# daughterboard.net
KiCad netlist of a schematic drawn in EAGLE
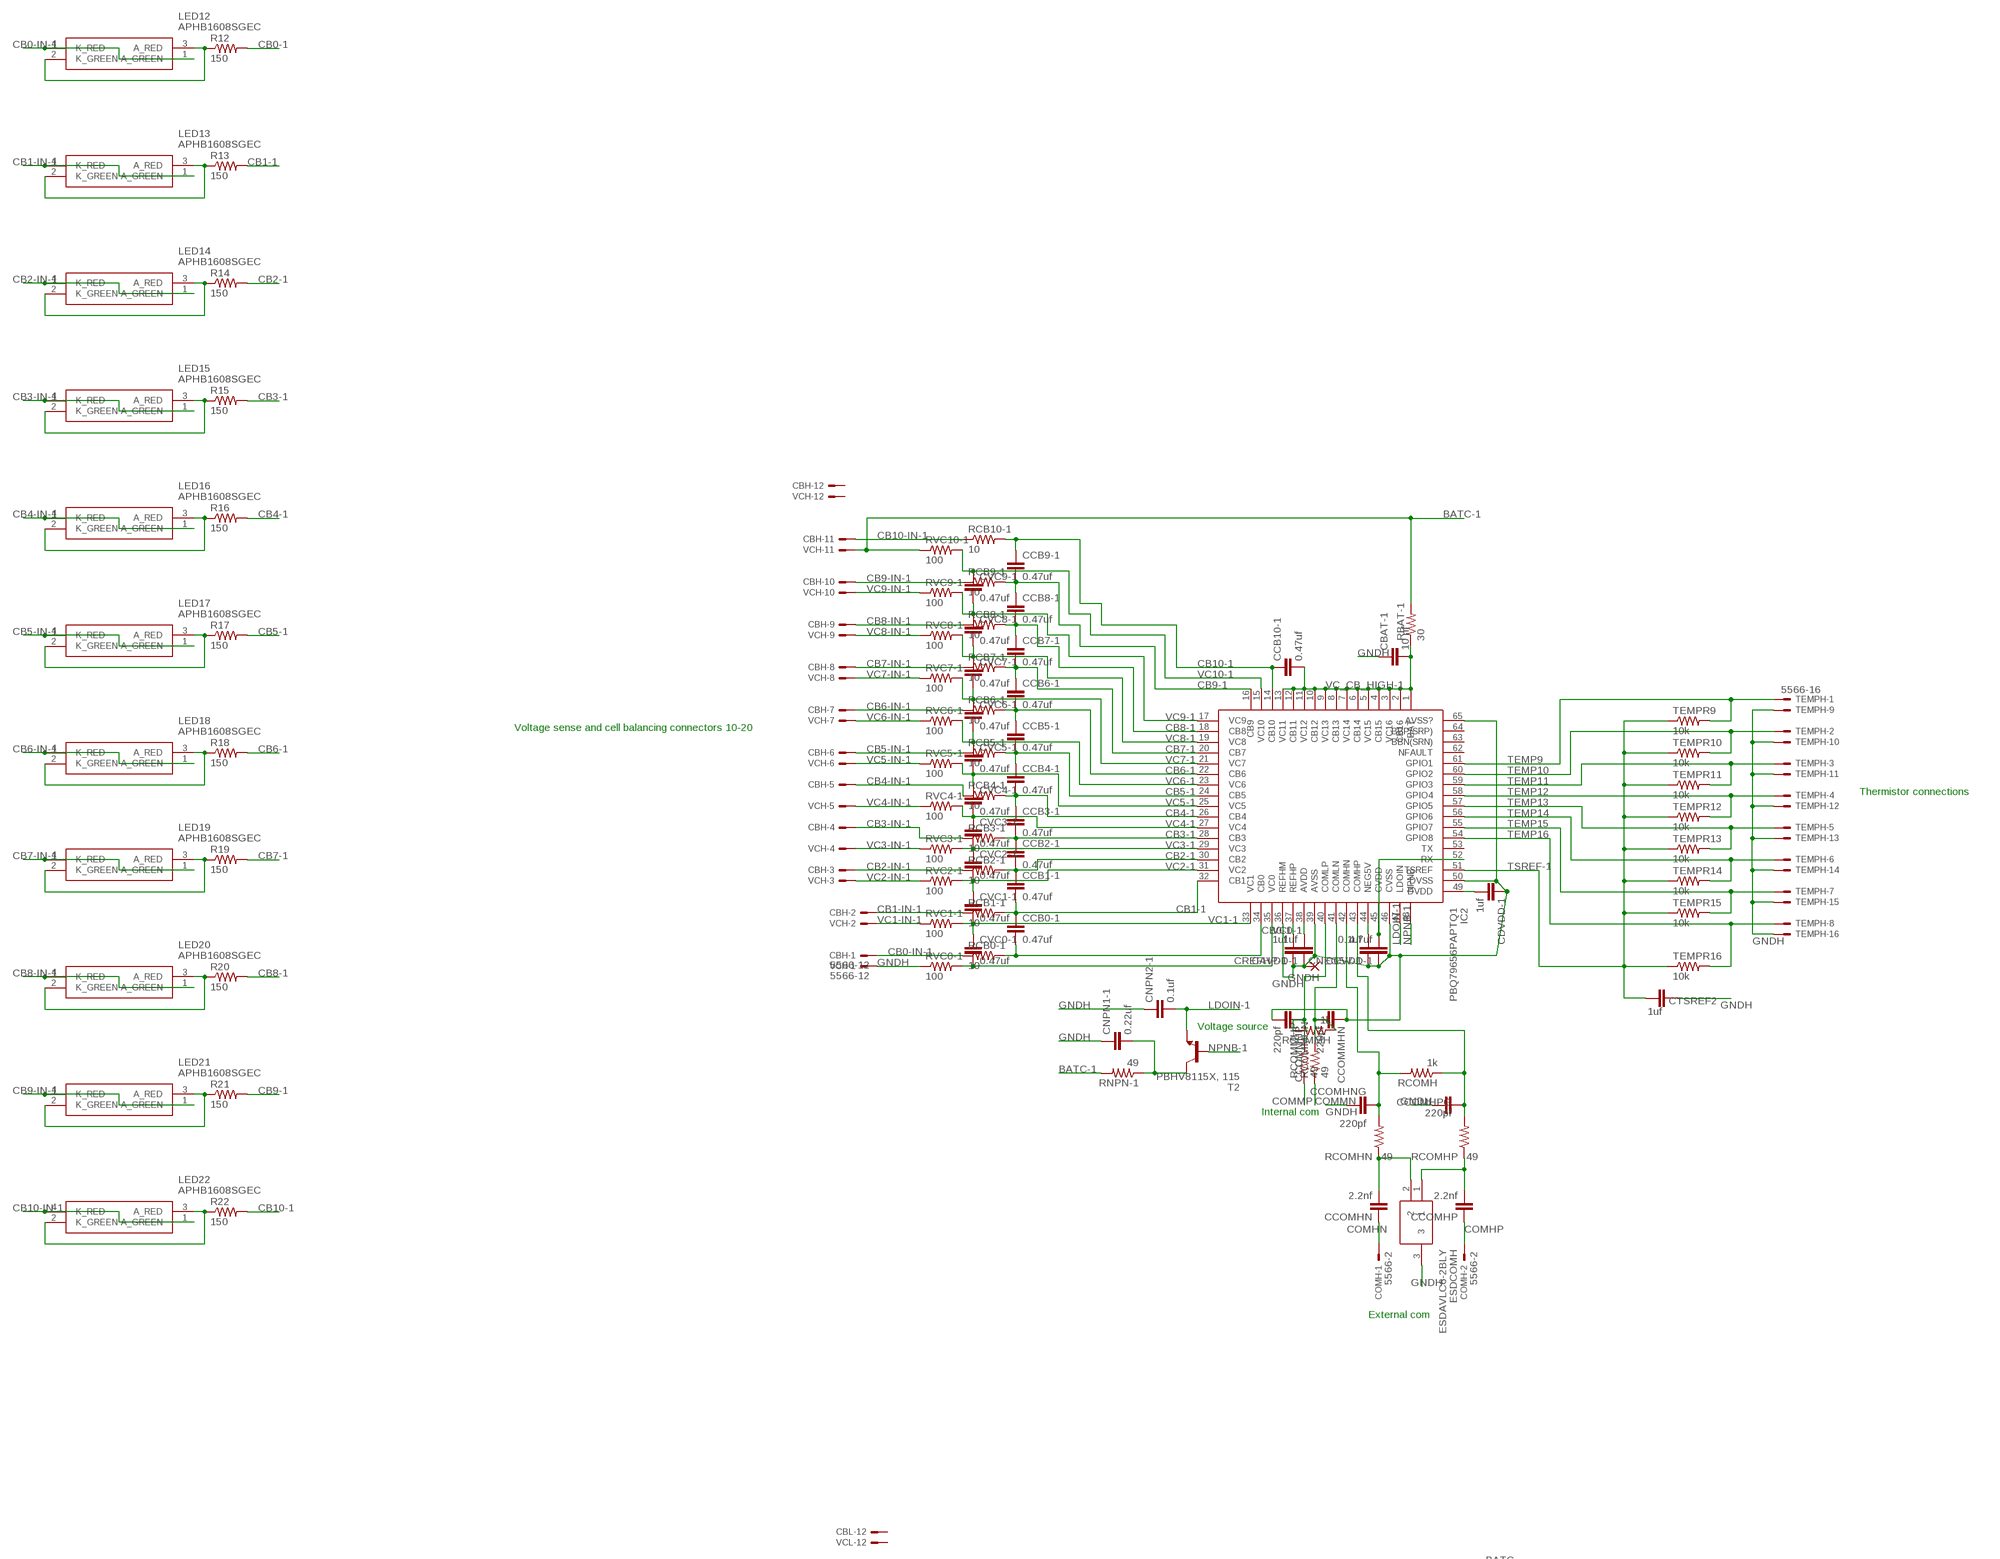
[diagram p0: schematic, sheet 1, part 1 of 2]
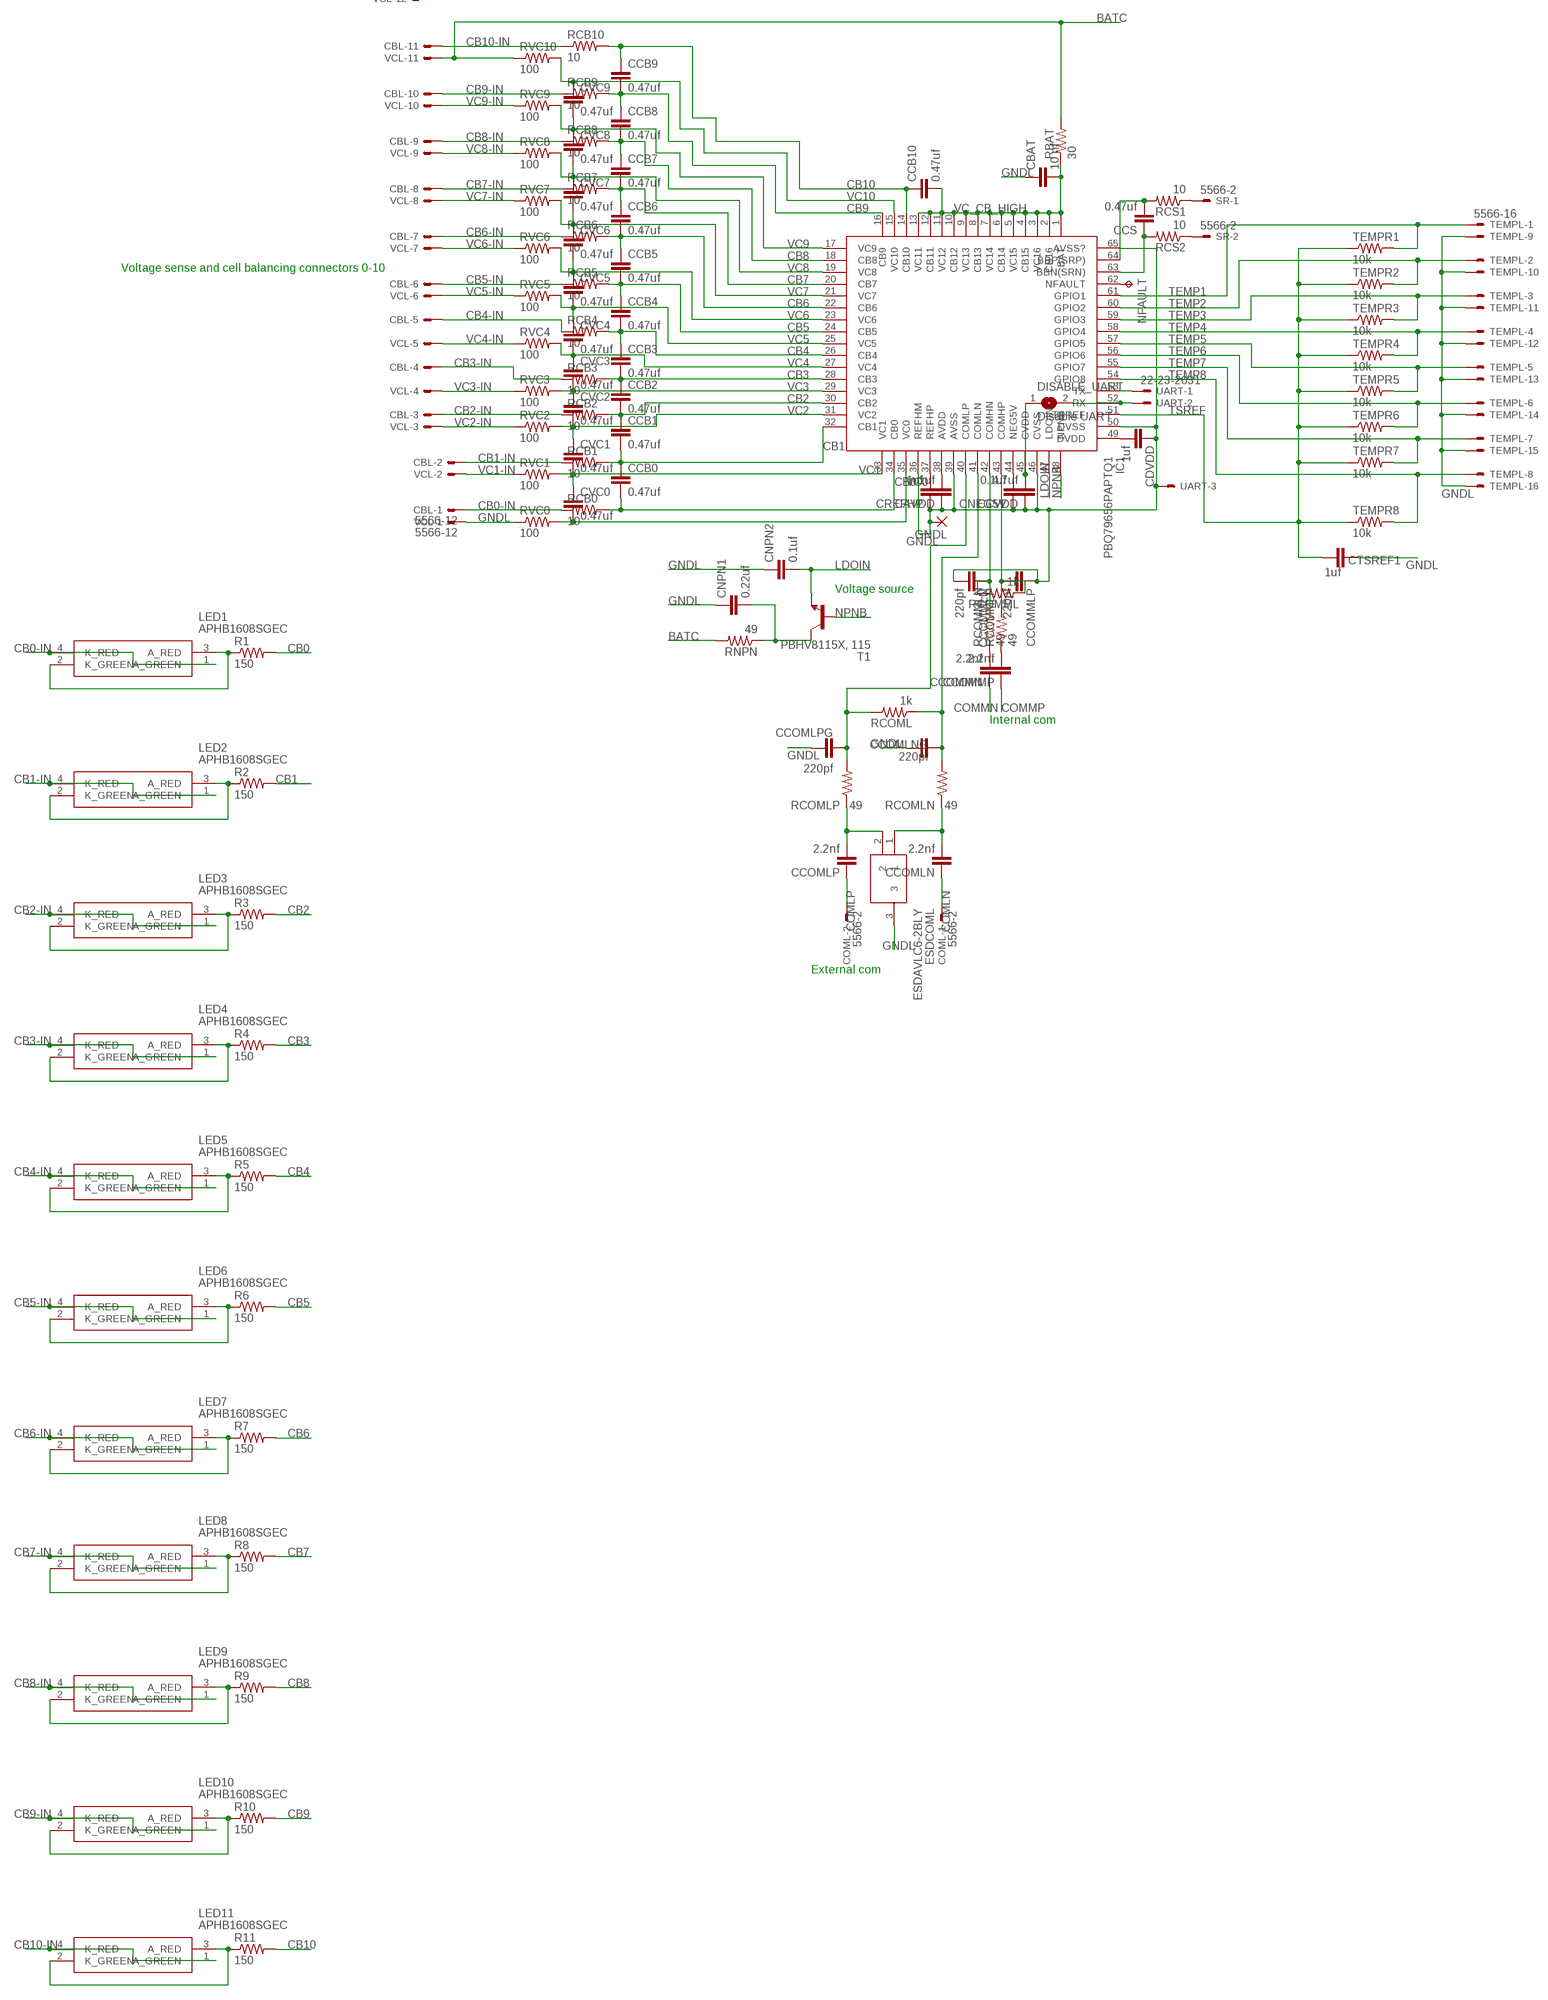
[diagram p1: schematic, sheet 1, part 2 of 2]

(export (version "E")
  (design (tool "Eeschema 10.0.6"))
  (components
    (comp (ref "CAVDD")
      (value "1uf")
      (footprint "eagle-import:C0603")
      (libsource (lib "eagle-import") (part "C-EUC0603"))
    )
    (comp (ref "CAVDD-1")
      (value "1uf")
      (footprint "eagle-import:C0603")
      (libsource (lib "eagle-import") (part "C-EUC0603"))
    )
    (comp (ref "CBAT")
      (value "10 nf")
      (footprint "eagle-import:C0603")
      (libsource (lib "eagle-import") (part "C-EUC0603"))
    )
    (comp (ref "CBAT-1")
      (value "10 nf")
      (footprint "eagle-import:C0603")
      (libsource (lib "eagle-import") (part "C-EUC0603"))
    )
    (comp (ref "CBH")
      (value "5566-12")
      (footprint "eagle-import:5566-12")
      (fields (field (name "MF") "MOLEX"))
      (libsource (lib "eagle-import") (part "5566-12"))
    )
    (comp (ref "CBL")
      (value "5566-12")
      (footprint "eagle-import:5566-12")
      (fields (field (name "MF") "MOLEX"))
      (libsource (lib "eagle-import") (part "5566-12"))
    )
    (comp (ref "CCB0")
      (value "0.47uf")
      (footprint "eagle-import:C0603")
      (libsource (lib "eagle-import") (part "C-EUC0603"))
    )
    (comp (ref "CCB0-1")
      (value "0.47uf")
      (footprint "eagle-import:C0603")
      (libsource (lib "eagle-import") (part "C-EUC0603"))
    )
    (comp (ref "CCB1")
      (value "0.47uf")
      (footprint "eagle-import:C0603")
      (libsource (lib "eagle-import") (part "C-EUC0603"))
    )
    (comp (ref "CCB1-1")
      (value "0.47uf")
      (footprint "eagle-import:C0603")
      (libsource (lib "eagle-import") (part "C-EUC0603"))
    )
    (comp (ref "CCB2")
      (value "0.47uf")
      (footprint "eagle-import:C0603")
      (libsource (lib "eagle-import") (part "C-EUC0603"))
    )
    (comp (ref "CCB2-1")
      (value "0.47uf")
      (footprint "eagle-import:C0603")
      (libsource (lib "eagle-import") (part "C-EUC0603"))
    )
    (comp (ref "CCB3")
      (value "0.47uf")
      (footprint "eagle-import:C0603")
      (libsource (lib "eagle-import") (part "C-EUC0603"))
    )
    (comp (ref "CCB3-1")
      (value "0.47uf")
      (footprint "eagle-import:C0603")
      (libsource (lib "eagle-import") (part "C-EUC0603"))
    )
    (comp (ref "CCB4")
      (value "0.47uf")
      (footprint "eagle-import:C0603")
      (libsource (lib "eagle-import") (part "C-EUC0603"))
    )
    (comp (ref "CCB4-1")
      (value "0.47uf")
      (footprint "eagle-import:C0603")
      (libsource (lib "eagle-import") (part "C-EUC0603"))
    )
    (comp (ref "CCB5")
      (value "0.47uf")
      (footprint "eagle-import:C0603")
      (libsource (lib "eagle-import") (part "C-EUC0603"))
    )
    (comp (ref "CCB5-1")
      (value "0.47uf")
      (footprint "eagle-import:C0603")
      (libsource (lib "eagle-import") (part "C-EUC0603"))
    )
    (comp (ref "CCB6")
      (value "0.47uf")
      (footprint "eagle-import:C0603")
      (libsource (lib "eagle-import") (part "C-EUC0603"))
    )
    (comp (ref "CCB6-1")
      (value "0.47uf")
      (footprint "eagle-import:C0603")
      (libsource (lib "eagle-import") (part "C-EUC0603"))
    )
    (comp (ref "CCB7")
      (value "0.47uf")
      (footprint "eagle-import:C0603")
      (libsource (lib "eagle-import") (part "C-EUC0603"))
    )
    (comp (ref "CCB7-1")
      (value "0.47uf")
      (footprint "eagle-import:C0603")
      (libsource (lib "eagle-import") (part "C-EUC0603"))
    )
    (comp (ref "CCB8")
      (value "0.47uf")
      (footprint "eagle-import:C0603")
      (libsource (lib "eagle-import") (part "C-EUC0603"))
    )
    (comp (ref "CCB8-1")
      (value "0.47uf")
      (footprint "eagle-import:C0603")
      (libsource (lib "eagle-import") (part "C-EUC0603"))
    )
    (comp (ref "CCB9")
      (value "0.47uf")
      (footprint "eagle-import:C0603")
      (libsource (lib "eagle-import") (part "C-EUC0603"))
    )
    (comp (ref "CCB9-1")
      (value "0.47uf")
      (footprint "eagle-import:C0603")
      (libsource (lib "eagle-import") (part "C-EUC0603"))
    )
    (comp (ref "CCB10")
      (value "0.47uf")
      (footprint "eagle-import:C0603")
      (libsource (lib "eagle-import") (part "C-EUC0603"))
    )
    (comp (ref "CCB10-1")
      (value "0.47uf")
      (footprint "eagle-import:C0603")
      (libsource (lib "eagle-import") (part "C-EUC0603"))
    )
    (comp (ref "CCOMHN")
      (value "2.2nf")
      (footprint "eagle-import:C0603")
      (libsource (lib "eagle-import") (part "C-EUC0603"))
    )
    (comp (ref "CCOMHNG")
      (value "220pf")
      (footprint "eagle-import:C0603")
      (libsource (lib "eagle-import") (part "C-EUC0603"))
    )
    (comp (ref "CCOMHP")
      (value "2.2nf")
      (footprint "eagle-import:C0603")
      (libsource (lib "eagle-import") (part "C-EUC0603"))
    )
    (comp (ref "CCOMHPG")
      (value "220pf")
      (footprint "eagle-import:C0603")
      (libsource (lib "eagle-import") (part "C-EUC0603"))
    )
    (comp (ref "CCOMLN")
      (value "2.2nf")
      (footprint "eagle-import:C0603")
      (libsource (lib "eagle-import") (part "C-EUC0603"))
    )
    (comp (ref "CCOMLNG")
      (value "220pf")
      (footprint "eagle-import:C0603")
      (libsource (lib "eagle-import") (part "C-EUC0603"))
    )
    (comp (ref "CCOMLP")
      (value "2.2nf")
      (footprint "eagle-import:C0603")
      (libsource (lib "eagle-import") (part "C-EUC0603"))
    )
    (comp (ref "CCOMLPG")
      (value "220pf")
      (footprint "eagle-import:C0603")
      (libsource (lib "eagle-import") (part "C-EUC0603"))
    )
    (comp (ref "CCOMMHN")
      (value "220pf")
      (footprint "eagle-import:C0603")
      (libsource (lib "eagle-import") (part "C-EUC0603"))
    )
    (comp (ref "CCOMMHP")
      (value "220pf")
      (footprint "eagle-import:C0603")
      (libsource (lib "eagle-import") (part "C-EUC0603"))
    )
    (comp (ref "CCOMMLN")
      (value "220pf")
      (footprint "eagle-import:C0603")
      (libsource (lib "eagle-import") (part "C-EUC0603"))
    )
    (comp (ref "CCOMMLP")
      (value "220pf")
      (footprint "eagle-import:C0603")
      (libsource (lib "eagle-import") (part "C-EUC0603"))
    )
    (comp (ref "CCOMMN")
      (value "2.2nf")
      (footprint "eagle-import:C0603")
      (libsource (lib "eagle-import") (part "C-EUC0603"))
    )
    (comp (ref "CCOMMP")
      (value "2.2nf")
      (footprint "eagle-import:C0603")
      (libsource (lib "eagle-import") (part "C-EUC0603"))
    )
    (comp (ref "CCS")
      (value "0.47uf")
      (footprint "eagle-import:C0603")
      (libsource (lib "eagle-import") (part "C-EUC0603"))
    )
    (comp (ref "CCVDD")
      (value "4.7uf")
      (footprint "eagle-import:C0603")
      (libsource (lib "eagle-import") (part "C-EUC0603"))
    )
    (comp (ref "CCVDD-1")
      (value "4.7uf")
      (footprint "eagle-import:C0603")
      (libsource (lib "eagle-import") (part "C-EUC0603"))
    )
    (comp (ref "CDVDD")
      (value "1uf")
      (footprint "eagle-import:C0603")
      (libsource (lib "eagle-import") (part "C-EUC0603"))
    )
    (comp (ref "CDVDD-1")
      (value "1uf")
      (footprint "eagle-import:C0603")
      (libsource (lib "eagle-import") (part "C-EUC0603"))
    )
    (comp (ref "CNEG5V")
      (value "0.1uf")
      (footprint "eagle-import:C0603")
      (libsource (lib "eagle-import") (part "C-EUC0603"))
    )
    (comp (ref "CNEG5V-1")
      (value "0.1uf")
      (footprint "eagle-import:C0603")
      (libsource (lib "eagle-import") (part "C-EUC0603"))
    )
    (comp (ref "CNPN1")
      (value "0.22uf")
      (footprint "eagle-import:C0603")
      (libsource (lib "eagle-import") (part "C-EUC0603"))
    )
    (comp (ref "CNPN1-1")
      (value "0.22uf")
      (footprint "eagle-import:C0603")
      (libsource (lib "eagle-import") (part "C-EUC0603"))
    )
    (comp (ref "CNPN2")
      (value "0.1uf")
      (footprint "eagle-import:C0603")
      (libsource (lib "eagle-import") (part "C-EUC0603"))
    )
    (comp (ref "CNPN2-1")
      (value "0.1uf")
      (footprint "eagle-import:C0603")
      (libsource (lib "eagle-import") (part "C-EUC0603"))
    )
    (comp (ref "COMH")
      (value "5566-2")
      (footprint "eagle-import:5566-2")
      (fields (field (name "MF") "MOLEX"))
      (libsource (lib "eagle-import") (part "5566-2"))
    )
    (comp (ref "COML")
      (value "5566-2")
      (footprint "eagle-import:5566-2")
      (fields (field (name "MF") "MOLEX"))
      (libsource (lib "eagle-import") (part "5566-2"))
    )
    (comp (ref "CREFHP")
      (value "1uf")
      (footprint "eagle-import:C0603")
      (libsource (lib "eagle-import") (part "C-EUC0603"))
    )
    (comp (ref "CREFHP-1")
      (value "1uf")
      (footprint "eagle-import:C0603")
      (libsource (lib "eagle-import") (part "C-EUC0603"))
    )
    (comp (ref "CTSREF1")
      (value "1uf")
      (footprint "eagle-import:C0603")
      (libsource (lib "eagle-import") (part "C-EUC0603"))
    )
    (comp (ref "CTSREF2")
      (value "1uf")
      (footprint "eagle-import:C0603")
      (libsource (lib "eagle-import") (part "C-EUC0603"))
    )
    (comp (ref "CVC0")
      (value "0.47uf")
      (footprint "eagle-import:C0603")
      (libsource (lib "eagle-import") (part "C-EUC0603"))
    )
    (comp (ref "CVC0-1")
      (value "0.47uf")
      (footprint "eagle-import:C0603")
      (libsource (lib "eagle-import") (part "C-EUC0603"))
    )
    (comp (ref "CVC1")
      (value "0.47uf")
      (footprint "eagle-import:C0603")
      (libsource (lib "eagle-import") (part "C-EUC0603"))
    )
    (comp (ref "CVC1-1")
      (value "0.47uf")
      (footprint "eagle-import:C0603")
      (libsource (lib "eagle-import") (part "C-EUC0603"))
    )
    (comp (ref "CVC2")
      (value "0.47uf")
      (footprint "eagle-import:C0603")
      (libsource (lib "eagle-import") (part "C-EUC0603"))
    )
    (comp (ref "CVC2-1")
      (value "0.47uf")
      (footprint "eagle-import:C0603")
      (libsource (lib "eagle-import") (part "C-EUC0603"))
    )
    (comp (ref "CVC3")
      (value "0.47uf")
      (footprint "eagle-import:C0603")
      (libsource (lib "eagle-import") (part "C-EUC0603"))
    )
    (comp (ref "CVC3-1")
      (value "0.47uf")
      (footprint "eagle-import:C0603")
      (libsource (lib "eagle-import") (part "C-EUC0603"))
    )
    (comp (ref "CVC4")
      (value "0.47uf")
      (footprint "eagle-import:C0603")
      (libsource (lib "eagle-import") (part "C-EUC0603"))
    )
    (comp (ref "CVC4-1")
      (value "0.47uf")
      (footprint "eagle-import:C0603")
      (libsource (lib "eagle-import") (part "C-EUC0603"))
    )
    (comp (ref "CVC5")
      (value "0.47uf")
      (footprint "eagle-import:C0603")
      (libsource (lib "eagle-import") (part "C-EUC0603"))
    )
    (comp (ref "CVC5-1")
      (value "0.47uf")
      (footprint "eagle-import:C0603")
      (libsource (lib "eagle-import") (part "C-EUC0603"))
    )
    (comp (ref "CVC6")
      (value "0.47uf")
      (footprint "eagle-import:C0603")
      (libsource (lib "eagle-import") (part "C-EUC0603"))
    )
    (comp (ref "CVC6-1")
      (value "0.47uf")
      (footprint "eagle-import:C0603")
      (libsource (lib "eagle-import") (part "C-EUC0603"))
    )
    (comp (ref "CVC7")
      (value "0.47uf")
      (footprint "eagle-import:C0603")
      (libsource (lib "eagle-import") (part "C-EUC0603"))
    )
    (comp (ref "CVC7-1")
      (value "0.47uf")
      (footprint "eagle-import:C0603")
      (libsource (lib "eagle-import") (part "C-EUC0603"))
    )
    (comp (ref "CVC8")
      (value "0.47uf")
      (footprint "eagle-import:C0603")
      (libsource (lib "eagle-import") (part "C-EUC0603"))
    )
    (comp (ref "CVC8-1")
      (value "0.47uf")
      (footprint "eagle-import:C0603")
      (libsource (lib "eagle-import") (part "C-EUC0603"))
    )
    (comp (ref "CVC9")
      (value "0.47uf")
      (footprint "eagle-import:C0603")
      (libsource (lib "eagle-import") (part "C-EUC0603"))
    )
    (comp (ref "CVC9-1")
      (value "0.47uf")
      (footprint "eagle-import:C0603")
      (libsource (lib "eagle-import") (part "C-EUC0603"))
    )
    (comp (ref "DISABLE_UART")
      (value "Disable UART")
      (footprint "eagle-import:SJ")
      (libsource (lib "eagle-import") (part "SJ"))
    )
    (comp (ref "ESDCOMH")
      (value "ESDAVLC6-2BLY")
      (footprint "eagle-import:SOT95P255X150-3N")
      (fields (field (name "MOUSER_PART_NUMBER") "511-ESDAVLC6-2BLY"))
      (libsource (lib "eagle-import") (part "ESDAVLC6-2BLY"))
    )
    (comp (ref "ESDCOML")
      (value "ESDAVLC6-2BLY")
      (footprint "eagle-import:SOT95P255X150-3N")
      (fields (field (name "MOUSER_PART_NUMBER") "511-ESDAVLC6-2BLY"))
      (libsource (lib "eagle-import") (part "ESDAVLC6-2BLY"))
    )
    (comp (ref "GNDH")
      (value "SMD5")
      (footprint "eagle-import:SMD2,54-5,08")
      (libsource (lib "eagle-import") (part "SMD5"))
    )
    (comp (ref "GNDL")
      (value "SMD5")
      (footprint "eagle-import:SMD2,54-5,08")
      (libsource (lib "eagle-import") (part "SMD5"))
    )
    (comp (ref "IC1")
      (value "PBQ79656PAPTQ1")
      (footprint "eagle-import:QFP50P1200X1200X120-65N")
      (libsource (lib "eagle-import") (part "PBQ79656PAPTQ1"))
    )
    (comp (ref "IC2")
      (value "PBQ79656PAPTQ1")
      (footprint "eagle-import:QFP50P1200X1200X120-65N")
      (libsource (lib "eagle-import") (part "PBQ79656PAPTQ1"))
    )
    (comp (ref "LED1")
      (value "APHB1608SGEC")
      (footprint "eagle-import:APHB1608SGEC")
      (fields (field (name "MOUSER_PART_NUMBER") "604-APHB1608SGEC"))
      (libsource (lib "eagle-import") (part "APHB1608SGEC"))
    )
    (comp (ref "LED2")
      (value "APHB1608SGEC")
      (footprint "eagle-import:APHB1608SGEC")
      (fields (field (name "MOUSER_PART_NUMBER") "604-APHB1608SGEC"))
      (libsource (lib "eagle-import") (part "APHB1608SGEC"))
    )
    (comp (ref "LED3")
      (value "APHB1608SGEC")
      (footprint "eagle-import:APHB1608SGEC")
      (fields (field (name "MOUSER_PART_NUMBER") "604-APHB1608SGEC"))
      (libsource (lib "eagle-import") (part "APHB1608SGEC"))
    )
    (comp (ref "LED4")
      (value "APHB1608SGEC")
      (footprint "eagle-import:APHB1608SGEC")
      (fields (field (name "MOUSER_PART_NUMBER") "604-APHB1608SGEC"))
      (libsource (lib "eagle-import") (part "APHB1608SGEC"))
    )
    (comp (ref "LED5")
      (value "APHB1608SGEC")
      (footprint "eagle-import:APHB1608SGEC")
      (fields (field (name "MOUSER_PART_NUMBER") "604-APHB1608SGEC"))
      (libsource (lib "eagle-import") (part "APHB1608SGEC"))
    )
    (comp (ref "LED6")
      (value "APHB1608SGEC")
      (footprint "eagle-import:APHB1608SGEC")
      (fields (field (name "MOUSER_PART_NUMBER") "604-APHB1608SGEC"))
      (libsource (lib "eagle-import") (part "APHB1608SGEC"))
    )
    (comp (ref "LED7")
      (value "APHB1608SGEC")
      (footprint "eagle-import:APHB1608SGEC")
      (fields (field (name "MOUSER_PART_NUMBER") "604-APHB1608SGEC"))
      (libsource (lib "eagle-import") (part "APHB1608SGEC"))
    )
    (comp (ref "LED8")
      (value "APHB1608SGEC")
      (footprint "eagle-import:APHB1608SGEC")
      (fields (field (name "MOUSER_PART_NUMBER") "604-APHB1608SGEC"))
      (libsource (lib "eagle-import") (part "APHB1608SGEC"))
    )
    (comp (ref "LED9")
      (value "APHB1608SGEC")
      (footprint "eagle-import:APHB1608SGEC")
      (fields (field (name "MOUSER_PART_NUMBER") "604-APHB1608SGEC"))
      (libsource (lib "eagle-import") (part "APHB1608SGEC"))
    )
    (comp (ref "LED10")
      (value "APHB1608SGEC")
      (footprint "eagle-import:APHB1608SGEC")
      (fields (field (name "MOUSER_PART_NUMBER") "604-APHB1608SGEC"))
      (libsource (lib "eagle-import") (part "APHB1608SGEC"))
    )
    (comp (ref "LED11")
      (value "APHB1608SGEC")
      (footprint "eagle-import:APHB1608SGEC")
      (fields (field (name "MOUSER_PART_NUMBER") "604-APHB1608SGEC"))
      (libsource (lib "eagle-import") (part "APHB1608SGEC"))
    )
    (comp (ref "LED12")
      (value "APHB1608SGEC")
      (footprint "eagle-import:APHB1608SGEC")
      (fields (field (name "MOUSER_PART_NUMBER") "604-APHB1608SGEC"))
      (libsource (lib "eagle-import") (part "APHB1608SGEC"))
    )
    (comp (ref "LED13")
      (value "APHB1608SGEC")
      (footprint "eagle-import:APHB1608SGEC")
      (fields (field (name "MOUSER_PART_NUMBER") "604-APHB1608SGEC"))
      (libsource (lib "eagle-import") (part "APHB1608SGEC"))
    )
    (comp (ref "LED14")
      (value "APHB1608SGEC")
      (footprint "eagle-import:APHB1608SGEC")
      (fields (field (name "MOUSER_PART_NUMBER") "604-APHB1608SGEC"))
      (libsource (lib "eagle-import") (part "APHB1608SGEC"))
    )
    (comp (ref "LED15")
      (value "APHB1608SGEC")
      (footprint "eagle-import:APHB1608SGEC")
      (fields (field (name "MOUSER_PART_NUMBER") "604-APHB1608SGEC"))
      (libsource (lib "eagle-import") (part "APHB1608SGEC"))
    )
    (comp (ref "LED16")
      (value "APHB1608SGEC")
      (footprint "eagle-import:APHB1608SGEC")
      (fields (field (name "MOUSER_PART_NUMBER") "604-APHB1608SGEC"))
      (libsource (lib "eagle-import") (part "APHB1608SGEC"))
    )
    (comp (ref "LED17")
      (value "APHB1608SGEC")
      (footprint "eagle-import:APHB1608SGEC")
      (fields (field (name "MOUSER_PART_NUMBER") "604-APHB1608SGEC"))
      (libsource (lib "eagle-import") (part "APHB1608SGEC"))
    )
    (comp (ref "LED18")
      (value "APHB1608SGEC")
      (footprint "eagle-import:APHB1608SGEC")
      (fields (field (name "MOUSER_PART_NUMBER") "604-APHB1608SGEC"))
      (libsource (lib "eagle-import") (part "APHB1608SGEC"))
    )
    (comp (ref "LED19")
      (value "APHB1608SGEC")
      (footprint "eagle-import:APHB1608SGEC")
      (fields (field (name "MOUSER_PART_NUMBER") "604-APHB1608SGEC"))
      (libsource (lib "eagle-import") (part "APHB1608SGEC"))
    )
    (comp (ref "LED20")
      (value "APHB1608SGEC")
      (footprint "eagle-import:APHB1608SGEC")
      (fields (field (name "MOUSER_PART_NUMBER") "604-APHB1608SGEC"))
      (libsource (lib "eagle-import") (part "APHB1608SGEC"))
    )
    (comp (ref "LED21")
      (value "APHB1608SGEC")
      (footprint "eagle-import:APHB1608SGEC")
      (fields (field (name "MOUSER_PART_NUMBER") "604-APHB1608SGEC"))
      (libsource (lib "eagle-import") (part "APHB1608SGEC"))
    )
    (comp (ref "LED22")
      (value "APHB1608SGEC")
      (footprint "eagle-import:APHB1608SGEC")
      (fields (field (name "MOUSER_PART_NUMBER") "604-APHB1608SGEC"))
      (libsource (lib "eagle-import") (part "APHB1608SGEC"))
    )
    (comp (ref "NFAULT")
      (value "TPB2,54")
      (footprint "eagle-import:B2,54")
      (libsource (lib "eagle-import") (part "TPB2,54"))
    )
    (comp (ref "R1")
      (value "150")
      (footprint "eagle-import:R0603")
      (libsource (lib "eagle-import") (part "R-US_R0603"))
    )
    (comp (ref "R2")
      (value "150")
      (footprint "eagle-import:R0603")
      (libsource (lib "eagle-import") (part "R-US_R0603"))
    )
    (comp (ref "R3")
      (value "150")
      (footprint "eagle-import:R0603")
      (libsource (lib "eagle-import") (part "R-US_R0603"))
    )
    (comp (ref "R4")
      (value "150")
      (footprint "eagle-import:R0603")
      (libsource (lib "eagle-import") (part "R-US_R0603"))
    )
    (comp (ref "R5")
      (value "150")
      (footprint "eagle-import:R0603")
      (libsource (lib "eagle-import") (part "R-US_R0603"))
    )
    (comp (ref "R6")
      (value "150")
      (footprint "eagle-import:R0603")
      (libsource (lib "eagle-import") (part "R-US_R0603"))
    )
    (comp (ref "R7")
      (value "150")
      (footprint "eagle-import:R0603")
      (libsource (lib "eagle-import") (part "R-US_R0603"))
    )
    (comp (ref "R8")
      (value "150")
      (footprint "eagle-import:R0603")
      (libsource (lib "eagle-import") (part "R-US_R0603"))
    )
    (comp (ref "R9")
      (value "150")
      (footprint "eagle-import:R0603")
      (libsource (lib "eagle-import") (part "R-US_R0603"))
    )
    (comp (ref "R10")
      (value "150")
      (footprint "eagle-import:R0603")
      (libsource (lib "eagle-import") (part "R-US_R0603"))
    )
    (comp (ref "R11")
      (value "150")
      (footprint "eagle-import:R0603")
      (libsource (lib "eagle-import") (part "R-US_R0603"))
    )
    (comp (ref "R12")
      (value "150")
      (footprint "eagle-import:R0603")
      (libsource (lib "eagle-import") (part "R-US_R0603"))
    )
    (comp (ref "R13")
      (value "150")
      (footprint "eagle-import:R0603")
      (libsource (lib "eagle-import") (part "R-US_R0603"))
    )
    (comp (ref "R14")
      (value "150")
      (footprint "eagle-import:R0603")
      (libsource (lib "eagle-import") (part "R-US_R0603"))
    )
    (comp (ref "R15")
      (value "150")
      (footprint "eagle-import:R0603")
      (libsource (lib "eagle-import") (part "R-US_R0603"))
    )
    (comp (ref "R16")
      (value "150")
      (footprint "eagle-import:R0603")
      (libsource (lib "eagle-import") (part "R-US_R0603"))
    )
    (comp (ref "R17")
      (value "150")
      (footprint "eagle-import:R0603")
      (libsource (lib "eagle-import") (part "R-US_R0603"))
    )
    (comp (ref "R18")
      (value "150")
      (footprint "eagle-import:R0603")
      (libsource (lib "eagle-import") (part "R-US_R0603"))
    )
    (comp (ref "R19")
      (value "150")
      (footprint "eagle-import:R0603")
      (libsource (lib "eagle-import") (part "R-US_R0603"))
    )
    (comp (ref "R20")
      (value "150")
      (footprint "eagle-import:R0603")
      (libsource (lib "eagle-import") (part "R-US_R0603"))
    )
    (comp (ref "R21")
      (value "150")
      (footprint "eagle-import:R0603")
      (libsource (lib "eagle-import") (part "R-US_R0603"))
    )
    (comp (ref "R22")
      (value "150")
      (footprint "eagle-import:R0603")
      (libsource (lib "eagle-import") (part "R-US_R0603"))
    )
    (comp (ref "RBAT")
      (value "30")
      (footprint "eagle-import:R0603")
      (libsource (lib "eagle-import") (part "R-US_R0603"))
    )
    (comp (ref "RBAT-1")
      (value "30")
      (footprint "eagle-import:R0603")
      (libsource (lib "eagle-import") (part "R-US_R0603"))
    )
    (comp (ref "RCB0")
      (value "10")
      (footprint "eagle-import:R1210")
      (libsource (lib "eagle-import") (part "R-US_R1210"))
    )
    (comp (ref "RCB0-1")
      (value "10")
      (footprint "eagle-import:R1210")
      (libsource (lib "eagle-import") (part "R-US_R1210"))
    )
    (comp (ref "RCB1")
      (value "10")
      (footprint "eagle-import:R1210")
      (libsource (lib "eagle-import") (part "R-US_R1210"))
    )
    (comp (ref "RCB1-1")
      (value "10")
      (footprint "eagle-import:R1210")
      (libsource (lib "eagle-import") (part "R-US_R1210"))
    )
    (comp (ref "RCB2")
      (value "10")
      (footprint "eagle-import:R1210")
      (libsource (lib "eagle-import") (part "R-US_R1210"))
    )
    (comp (ref "RCB2-1")
      (value "10")
      (footprint "eagle-import:R1210")
      (libsource (lib "eagle-import") (part "R-US_R1210"))
    )
    (comp (ref "RCB3")
      (value "10")
      (footprint "eagle-import:R1210")
      (libsource (lib "eagle-import") (part "R-US_R1210"))
    )
    (comp (ref "RCB3-1")
      (value "10")
      (footprint "eagle-import:R1210")
      (libsource (lib "eagle-import") (part "R-US_R1210"))
    )
    (comp (ref "RCB4")
      (value "10")
      (footprint "eagle-import:R1210")
      (libsource (lib "eagle-import") (part "R-US_R1210"))
    )
    (comp (ref "RCB4-1")
      (value "10")
      (footprint "eagle-import:R1210")
      (libsource (lib "eagle-import") (part "R-US_R1210"))
    )
    (comp (ref "RCB5")
      (value "10")
      (footprint "eagle-import:R1210")
      (libsource (lib "eagle-import") (part "R-US_R1210"))
    )
    (comp (ref "RCB5-1")
      (value "10")
      (footprint "eagle-import:R1210")
      (libsource (lib "eagle-import") (part "R-US_R1210"))
    )
    (comp (ref "RCB6")
      (value "10")
      (footprint "eagle-import:R1210")
      (libsource (lib "eagle-import") (part "R-US_R1210"))
    )
    (comp (ref "RCB6-1")
      (value "10")
      (footprint "eagle-import:R1210")
      (libsource (lib "eagle-import") (part "R-US_R1210"))
    )
    (comp (ref "RCB7")
      (value "10")
      (footprint "eagle-import:R1210")
      (libsource (lib "eagle-import") (part "R-US_R1210"))
    )
    (comp (ref "RCB7-1")
      (value "10")
      (footprint "eagle-import:R1210")
      (libsource (lib "eagle-import") (part "R-US_R1210"))
    )
    (comp (ref "RCB8")
      (value "10")
      (footprint "eagle-import:R1210")
      (libsource (lib "eagle-import") (part "R-US_R1210"))
    )
    (comp (ref "RCB8-1")
      (value "10")
      (footprint "eagle-import:R1210")
      (libsource (lib "eagle-import") (part "R-US_R1210"))
    )
    (comp (ref "RCB9")
      (value "10")
      (footprint "eagle-import:R1210")
      (libsource (lib "eagle-import") (part "R-US_R1210"))
    )
    (comp (ref "RCB9-1")
      (value "10")
      (footprint "eagle-import:R1210")
      (libsource (lib "eagle-import") (part "R-US_R1210"))
    )
    (comp (ref "RCB10")
      (value "10")
      (footprint "eagle-import:R1210")
      (libsource (lib "eagle-import") (part "R-US_R1210"))
    )
    (comp (ref "RCB10-1")
      (value "10")
      (footprint "eagle-import:R1210")
      (libsource (lib "eagle-import") (part "R-US_R1210"))
    )
    (comp (ref "RCOMH")
      (value "1k")
      (footprint "eagle-import:R0603")
      (libsource (lib "eagle-import") (part "R-US_R0603"))
    )
    (comp (ref "RCOMHN")
      (value "49")
      (footprint "eagle-import:R0603")
      (libsource (lib "eagle-import") (part "R-US_R0603"))
    )
    (comp (ref "RCOMHP")
      (value "49")
      (footprint "eagle-import:R0603")
      (libsource (lib "eagle-import") (part "R-US_R0603"))
    )
    (comp (ref "RCOML")
      (value "1k")
      (footprint "eagle-import:R0603")
      (libsource (lib "eagle-import") (part "R-US_R0603"))
    )
    (comp (ref "RCOMLN")
      (value "49")
      (footprint "eagle-import:R0603")
      (libsource (lib "eagle-import") (part "R-US_R0603"))
    )
    (comp (ref "RCOMLP")
      (value "49")
      (footprint "eagle-import:R0603")
      (libsource (lib "eagle-import") (part "R-US_R0603"))
    )
    (comp (ref "RCOMMH")
      (value "1k")
      (footprint "eagle-import:R0603")
      (libsource (lib "eagle-import") (part "R-US_R0603"))
    )
    (comp (ref "RCOMMHN")
      (value "49")
      (footprint "eagle-import:R0603")
      (libsource (lib "eagle-import") (part "R-US_R0603"))
    )
    (comp (ref "RCOMMHP")
      (value "49")
      (footprint "eagle-import:R0603")
      (libsource (lib "eagle-import") (part "R-US_R0603"))
    )
    (comp (ref "RCOMML")
      (value "1k")
      (footprint "eagle-import:R0603")
      (libsource (lib "eagle-import") (part "R-US_R0603"))
    )
    (comp (ref "RCOMMLN")
      (value "49")
      (footprint "eagle-import:R0603")
      (libsource (lib "eagle-import") (part "R-US_R0603"))
    )
    (comp (ref "RCOMMLP")
      (value "49")
      (footprint "eagle-import:R0603")
      (libsource (lib "eagle-import") (part "R-US_R0603"))
    )
    (comp (ref "RCS1")
      (value "10")
      (footprint "eagle-import:R0603")
      (libsource (lib "eagle-import") (part "R-US_R0603"))
    )
    (comp (ref "RCS2")
      (value "10")
      (footprint "eagle-import:R0603")
      (libsource (lib "eagle-import") (part "R-US_R0603"))
    )
    (comp (ref "RNPN")
      (value "49")
      (footprint "eagle-import:R0603")
      (libsource (lib "eagle-import") (part "R-US_R0603"))
    )
    (comp (ref "RNPN-1")
      (value "49")
      (footprint "eagle-import:R0603")
      (libsource (lib "eagle-import") (part "R-US_R0603"))
    )
    (comp (ref "RVC0")
      (value "100")
      (footprint "eagle-import:R0603")
      (libsource (lib "eagle-import") (part "R-US_R0603"))
    )
    (comp (ref "RVC0-1")
      (value "100")
      (footprint "eagle-import:R0603")
      (libsource (lib "eagle-import") (part "R-US_R0603"))
    )
    (comp (ref "RVC1")
      (value "100")
      (footprint "eagle-import:R0603")
      (libsource (lib "eagle-import") (part "R-US_R0603"))
    )
    (comp (ref "RVC1-1")
      (value "100")
      (footprint "eagle-import:R0603")
      (libsource (lib "eagle-import") (part "R-US_R0603"))
    )
    (comp (ref "RVC2")
      (value "100")
      (footprint "eagle-import:R0603")
      (libsource (lib "eagle-import") (part "R-US_R0603"))
    )
    (comp (ref "RVC2-1")
      (value "100")
      (footprint "eagle-import:R0603")
      (libsource (lib "eagle-import") (part "R-US_R0603"))
    )
    (comp (ref "RVC3")
      (value "100")
      (footprint "eagle-import:R0603")
      (libsource (lib "eagle-import") (part "R-US_R0603"))
    )
    (comp (ref "RVC3-1")
      (value "100")
      (footprint "eagle-import:R0603")
      (libsource (lib "eagle-import") (part "R-US_R0603"))
    )
    (comp (ref "RVC4")
      (value "100")
      (footprint "eagle-import:R0603")
      (libsource (lib "eagle-import") (part "R-US_R0603"))
    )
    (comp (ref "RVC4-1")
      (value "100")
      (footprint "eagle-import:R0603")
      (libsource (lib "eagle-import") (part "R-US_R0603"))
    )
    (comp (ref "RVC5")
      (value "100")
      (footprint "eagle-import:R0603")
      (libsource (lib "eagle-import") (part "R-US_R0603"))
    )
    (comp (ref "RVC5-1")
      (value "100")
      (footprint "eagle-import:R0603")
      (libsource (lib "eagle-import") (part "R-US_R0603"))
    )
    (comp (ref "RVC6")
      (value "100")
      (footprint "eagle-import:R0603")
      (libsource (lib "eagle-import") (part "R-US_R0603"))
    )
    (comp (ref "RVC6-1")
      (value "100")
      (footprint "eagle-import:R0603")
      (libsource (lib "eagle-import") (part "R-US_R0603"))
    )
    (comp (ref "RVC7")
      (value "100")
      (footprint "eagle-import:R0603")
      (libsource (lib "eagle-import") (part "R-US_R0603"))
    )
    (comp (ref "RVC7-1")
      (value "100")
      (footprint "eagle-import:R0603")
      (libsource (lib "eagle-import") (part "R-US_R0603"))
    )
    (comp (ref "RVC8")
      (value "100")
      (footprint "eagle-import:R0603")
      (libsource (lib "eagle-import") (part "R-US_R0603"))
    )
    (comp (ref "RVC8-1")
      (value "100")
      (footprint "eagle-import:R0603")
      (libsource (lib "eagle-import") (part "R-US_R0603"))
    )
    (comp (ref "RVC9")
      (value "100")
      (footprint "eagle-import:R0603")
      (libsource (lib "eagle-import") (part "R-US_R0603"))
    )
    (comp (ref "RVC9-1")
      (value "100")
      (footprint "eagle-import:R0603")
      (libsource (lib "eagle-import") (part "R-US_R0603"))
    )
    (comp (ref "RVC10")
      (value "100")
      (footprint "eagle-import:R0603")
      (libsource (lib "eagle-import") (part "R-US_R0603"))
    )
    (comp (ref "RVC10-1")
      (value "100")
      (footprint "eagle-import:R0603")
      (libsource (lib "eagle-import") (part "R-US_R0603"))
    )
    (comp (ref "SR")
      (value "5566-2")
      (footprint "eagle-import:5566-2")
      (fields (field (name "MF") "MOLEX"))
      (libsource (lib "eagle-import") (part "5566-2"))
    )
    (comp (ref "T1")
      (value "PBHV8115X, 115")
      (footprint "eagle-import:SOT89-BCE")
      (libsource (lib "eagle-import") (part "-NPN-SOT89-BCEBC868"))
    )
    (comp (ref "T2")
      (value "PBHV8115X, 115")
      (footprint "eagle-import:SOT89-BCE")
      (libsource (lib "eagle-import") (part "-NPN-SOT89-BCEBC868"))
    )
    (comp (ref "TEMPH")
      (value "5566-16")
      (footprint "eagle-import:5566-16")
      (fields (field (name "MF") "MOLEX"))
      (libsource (lib "eagle-import") (part "5566-16"))
    )
    (comp (ref "TEMPL")
      (value "5566-16")
      (footprint "eagle-import:5566-16")
      (fields (field (name "MF") "MOLEX"))
      (libsource (lib "eagle-import") (part "5566-16"))
    )
    (comp (ref "TEMPR1")
      (value "10k")
      (footprint "eagle-import:R0603")
      (libsource (lib "eagle-import") (part "R-US_R0603"))
    )
    (comp (ref "TEMPR2")
      (value "10k")
      (footprint "eagle-import:R0603")
      (libsource (lib "eagle-import") (part "R-US_R0603"))
    )
    (comp (ref "TEMPR3")
      (value "10k")
      (footprint "eagle-import:R0603")
      (libsource (lib "eagle-import") (part "R-US_R0603"))
    )
    (comp (ref "TEMPR4")
      (value "10k")
      (footprint "eagle-import:R0603")
      (libsource (lib "eagle-import") (part "R-US_R0603"))
    )
    (comp (ref "TEMPR5")
      (value "10k")
      (footprint "eagle-import:R0603")
      (libsource (lib "eagle-import") (part "R-US_R0603"))
    )
    (comp (ref "TEMPR6")
      (value "10k")
      (footprint "eagle-import:R0603")
      (libsource (lib "eagle-import") (part "R-US_R0603"))
    )
    (comp (ref "TEMPR7")
      (value "10k")
      (footprint "eagle-import:R0603")
      (libsource (lib "eagle-import") (part "R-US_R0603"))
    )
    (comp (ref "TEMPR8")
      (value "10k")
      (footprint "eagle-import:R0603")
      (libsource (lib "eagle-import") (part "R-US_R0603"))
    )
    (comp (ref "TEMPR9")
      (value "10k")
      (footprint "eagle-import:R0603")
      (libsource (lib "eagle-import") (part "R-US_R0603"))
    )
    (comp (ref "TEMPR10")
      (value "10k")
      (footprint "eagle-import:R0603")
      (libsource (lib "eagle-import") (part "R-US_R0603"))
    )
    (comp (ref "TEMPR11")
      (value "10k")
      (footprint "eagle-import:R0603")
      (libsource (lib "eagle-import") (part "R-US_R0603"))
    )
    (comp (ref "TEMPR12")
      (value "10k")
      (footprint "eagle-import:R0603")
      (libsource (lib "eagle-import") (part "R-US_R0603"))
    )
    (comp (ref "TEMPR13")
      (value "10k")
      (footprint "eagle-import:R0603")
      (libsource (lib "eagle-import") (part "R-US_R0603"))
    )
    (comp (ref "TEMPR14")
      (value "10k")
      (footprint "eagle-import:R0603")
      (libsource (lib "eagle-import") (part "R-US_R0603"))
    )
    (comp (ref "TEMPR15")
      (value "10k")
      (footprint "eagle-import:R0603")
      (libsource (lib "eagle-import") (part "R-US_R0603"))
    )
    (comp (ref "TEMPR16")
      (value "10k")
      (footprint "eagle-import:R0603")
      (libsource (lib "eagle-import") (part "R-US_R0603"))
    )
    (comp (ref "UART")
      (value "22-23-2031")
      (footprint "eagle-import:22-23-2031")
      (fields (field (name "MF") "MOLEX"))
      (libsource (lib "eagle-import") (part "22-23-2031"))
    )
    (comp (ref "VCH")
      (value "5566-12")
      (footprint "eagle-import:5566-12")
      (fields (field (name "MF") "MOLEX"))
      (libsource (lib "eagle-import") (part "5566-12"))
    )
    (comp (ref "VCL")
      (value "5566-12")
      (footprint "eagle-import:5566-12")
      (fields (field (name "MF") "MOLEX"))
      (libsource (lib "eagle-import") (part "5566-12"))
    )
  )
  (nets
    (net (code "1") (name "/BATC") (class "Default")
      (node (ref "RBAT") (pin "2") (pinfunction "2_2") (pintype "passive"))
      (node (ref "RNPN") (pin "2") (pinfunction "2_2") (pintype "passive"))
      (node (ref "RVC10") (pin "1") (pinfunction "1_1") (pintype "passive"))
      (node (ref "VCL") (pin "11") (pinfunction "S_11") (pintype "passive"))
    )
    (net (code "2") (name "/BATC-1") (class "Default")
      (node (ref "RBAT-1") (pin "2") (pinfunction "2_2") (pintype "passive"))
      (node (ref "RNPN-1") (pin "2") (pinfunction "2_2") (pintype "passive"))
      (node (ref "RVC10-1") (pin "1") (pinfunction "1_1") (pintype "passive"))
      (node (ref "VCH") (pin "11") (pinfunction "S_11") (pintype "passive"))
    )
    (net (code "3") (name "/CB0") (class "Default")
      (node (ref "CCB0") (pin "2") (pinfunction "2_2") (pintype "passive"))
      (node (ref "IC1") (pin "34") (pinfunction "CB0_34") (pintype "bidirectional"))
      (node (ref "R1") (pin "2") (pinfunction "2_2") (pintype "passive"))
      (node (ref "RCB0") (pin "2") (pinfunction "2_2") (pintype "passive"))
    )
    (net (code "4") (name "/CB0-1") (class "Default")
      (node (ref "CCB0-1") (pin "2") (pinfunction "2_2") (pintype "passive"))
      (node (ref "IC2") (pin "34") (pinfunction "CB0_34") (pintype "bidirectional"))
      (node (ref "R12") (pin "2") (pinfunction "2_2") (pintype "passive"))
      (node (ref "RCB0-1") (pin "2") (pinfunction "2_2") (pintype "passive"))
    )
    (net (code "5") (name "/CB0-IN") (class "Default")
      (node (ref "CBL") (pin "1") (pinfunction "S_1") (pintype "passive"))
      (node (ref "LED1") (pin "1") (pinfunction "A_GREEN_1") (pintype "bidirectional"))
      (node (ref "LED1") (pin "4") (pinfunction "K_RED_4") (pintype "bidirectional"))
      (node (ref "RCB0") (pin "1") (pinfunction "1_1") (pintype "passive"))
    )
    (net (code "6") (name "/CB0-IN-1") (class "Default")
      (node (ref "CBH") (pin "1") (pinfunction "S_1") (pintype "passive"))
      (node (ref "LED12") (pin "1") (pinfunction "A_GREEN_1") (pintype "bidirectional"))
      (node (ref "LED12") (pin "4") (pinfunction "K_RED_4") (pintype "bidirectional"))
      (node (ref "RCB0-1") (pin "1") (pinfunction "1_1") (pintype "passive"))
    )
    (net (code "7") (name "/CB1") (class "Default")
      (node (ref "CCB0") (pin "1") (pinfunction "1_1") (pintype "passive"))
      (node (ref "CCB1") (pin "2") (pinfunction "2_2") (pintype "passive"))
      (node (ref "IC1") (pin "32") (pinfunction "CB1_32") (pintype "bidirectional"))
      (node (ref "R2") (pin "2") (pinfunction "2_2") (pintype "passive"))
      (node (ref "RCB1") (pin "2") (pinfunction "2_2") (pintype "passive"))
    )
    (net (code "8") (name "/CB1-1") (class "Default")
      (node (ref "CCB0-1") (pin "1") (pinfunction "1_1") (pintype "passive"))
      (node (ref "CCB1-1") (pin "2") (pinfunction "2_2") (pintype "passive"))
      (node (ref "IC2") (pin "32") (pinfunction "CB1_32") (pintype "bidirectional"))
      (node (ref "R13") (pin "2") (pinfunction "2_2") (pintype "passive"))
      (node (ref "RCB1-1") (pin "2") (pinfunction "2_2") (pintype "passive"))
    )
    (net (code "9") (name "/CB1-IN") (class "Default")
      (node (ref "CBL") (pin "2") (pinfunction "S_2") (pintype "passive"))
      (node (ref "LED2") (pin "1") (pinfunction "A_GREEN_1") (pintype "bidirectional"))
      (node (ref "LED2") (pin "4") (pinfunction "K_RED_4") (pintype "bidirectional"))
      (node (ref "RCB1") (pin "1") (pinfunction "1_1") (pintype "passive"))
    )
    (net (code "10") (name "/CB1-IN-1") (class "Default")
      (node (ref "CBH") (pin "2") (pinfunction "S_2") (pintype "passive"))
      (node (ref "LED13") (pin "1") (pinfunction "A_GREEN_1") (pintype "bidirectional"))
      (node (ref "LED13") (pin "4") (pinfunction "K_RED_4") (pintype "bidirectional"))
      (node (ref "RCB1-1") (pin "1") (pinfunction "1_1") (pintype "passive"))
    )
    (net (code "11") (name "/CB2") (class "Default")
      (node (ref "CCB1") (pin "1") (pinfunction "1_1") (pintype "passive"))
      (node (ref "CCB2") (pin "2") (pinfunction "2_2") (pintype "passive"))
      (node (ref "IC1") (pin "30") (pinfunction "CB2_30") (pintype "bidirectional"))
      (node (ref "R3") (pin "2") (pinfunction "2_2") (pintype "passive"))
      (node (ref "RCB2") (pin "2") (pinfunction "2_2") (pintype "passive"))
    )
    (net (code "12") (name "/CB2-1") (class "Default")
      (node (ref "CCB1-1") (pin "1") (pinfunction "1_1") (pintype "passive"))
      (node (ref "CCB2-1") (pin "2") (pinfunction "2_2") (pintype "passive"))
      (node (ref "IC2") (pin "30") (pinfunction "CB2_30") (pintype "bidirectional"))
      (node (ref "R14") (pin "2") (pinfunction "2_2") (pintype "passive"))
      (node (ref "RCB2-1") (pin "2") (pinfunction "2_2") (pintype "passive"))
    )
    (net (code "13") (name "/CB2-IN") (class "Default")
      (node (ref "CBL") (pin "3") (pinfunction "S_3") (pintype "passive"))
      (node (ref "LED3") (pin "1") (pinfunction "A_GREEN_1") (pintype "bidirectional"))
      (node (ref "LED3") (pin "4") (pinfunction "K_RED_4") (pintype "bidirectional"))
      (node (ref "RCB2") (pin "1") (pinfunction "1_1") (pintype "passive"))
    )
    (net (code "14") (name "/CB2-IN-1") (class "Default")
      (node (ref "CBH") (pin "3") (pinfunction "S_3") (pintype "passive"))
      (node (ref "LED14") (pin "1") (pinfunction "A_GREEN_1") (pintype "bidirectional"))
      (node (ref "LED14") (pin "4") (pinfunction "K_RED_4") (pintype "bidirectional"))
      (node (ref "RCB2-1") (pin "1") (pinfunction "1_1") (pintype "passive"))
    )
    (net (code "15") (name "/CB3") (class "Default")
      (node (ref "CCB2") (pin "1") (pinfunction "1_1") (pintype "passive"))
      (node (ref "CCB3") (pin "2") (pinfunction "2_2") (pintype "passive"))
      (node (ref "IC1") (pin "28") (pinfunction "CB3_28") (pintype "bidirectional"))
      (node (ref "R4") (pin "2") (pinfunction "2_2") (pintype "passive"))
      (node (ref "RCB3") (pin "2") (pinfunction "2_2") (pintype "passive"))
    )
    (net (code "16") (name "/CB3-1") (class "Default")
      (node (ref "CCB2-1") (pin "1") (pinfunction "1_1") (pintype "passive"))
      (node (ref "CCB3-1") (pin "2") (pinfunction "2_2") (pintype "passive"))
      (node (ref "IC2") (pin "28") (pinfunction "CB3_28") (pintype "bidirectional"))
      (node (ref "R15") (pin "2") (pinfunction "2_2") (pintype "passive"))
      (node (ref "RCB3-1") (pin "2") (pinfunction "2_2") (pintype "passive"))
    )
    (net (code "17") (name "/CB3-IN") (class "Default")
      (node (ref "CBL") (pin "4") (pinfunction "S_4") (pintype "passive"))
      (node (ref "LED4") (pin "1") (pinfunction "A_GREEN_1") (pintype "bidirectional"))
      (node (ref "LED4") (pin "4") (pinfunction "K_RED_4") (pintype "bidirectional"))
      (node (ref "RCB3") (pin "1") (pinfunction "1_1") (pintype "passive"))
    )
    (net (code "18") (name "/CB3-IN-1") (class "Default")
      (node (ref "CBH") (pin "4") (pinfunction "S_4") (pintype "passive"))
      (node (ref "LED15") (pin "1") (pinfunction "A_GREEN_1") (pintype "bidirectional"))
      (node (ref "LED15") (pin "4") (pinfunction "K_RED_4") (pintype "bidirectional"))
      (node (ref "RCB3-1") (pin "1") (pinfunction "1_1") (pintype "passive"))
    )
    (net (code "19") (name "/CB4") (class "Default")
      (node (ref "CCB3") (pin "1") (pinfunction "1_1") (pintype "passive"))
      (node (ref "CCB4") (pin "2") (pinfunction "2_2") (pintype "passive"))
      (node (ref "IC1") (pin "26") (pinfunction "CB4_26") (pintype "bidirectional"))
      (node (ref "R5") (pin "2") (pinfunction "2_2") (pintype "passive"))
      (node (ref "RCB4") (pin "2") (pinfunction "2_2") (pintype "passive"))
    )
    (net (code "20") (name "/CB4-1") (class "Default")
      (node (ref "CCB3-1") (pin "1") (pinfunction "1_1") (pintype "passive"))
      (node (ref "CCB4-1") (pin "2") (pinfunction "2_2") (pintype "passive"))
      (node (ref "IC2") (pin "26") (pinfunction "CB4_26") (pintype "bidirectional"))
      (node (ref "R16") (pin "2") (pinfunction "2_2") (pintype "passive"))
      (node (ref "RCB4-1") (pin "2") (pinfunction "2_2") (pintype "passive"))
    )
    (net (code "21") (name "/CB4-IN") (class "Default")
      (node (ref "CBL") (pin "5") (pinfunction "S_5") (pintype "passive"))
      (node (ref "LED5") (pin "1") (pinfunction "A_GREEN_1") (pintype "bidirectional"))
      (node (ref "LED5") (pin "4") (pinfunction "K_RED_4") (pintype "bidirectional"))
      (node (ref "RCB4") (pin "1") (pinfunction "1_1") (pintype "passive"))
    )
    (net (code "22") (name "/CB4-IN-1") (class "Default")
      (node (ref "CBH") (pin "5") (pinfunction "S_5") (pintype "passive"))
      (node (ref "LED16") (pin "1") (pinfunction "A_GREEN_1") (pintype "bidirectional"))
      (node (ref "LED16") (pin "4") (pinfunction "K_RED_4") (pintype "bidirectional"))
      (node (ref "RCB4-1") (pin "1") (pinfunction "1_1") (pintype "passive"))
    )
    (net (code "23") (name "/CB5") (class "Default")
      (node (ref "CCB4") (pin "1") (pinfunction "1_1") (pintype "passive"))
      (node (ref "CCB5") (pin "2") (pinfunction "2_2") (pintype "passive"))
      (node (ref "IC1") (pin "24") (pinfunction "CB5_24") (pintype "bidirectional"))
      (node (ref "R6") (pin "2") (pinfunction "2_2") (pintype "passive"))
      (node (ref "RCB5") (pin "2") (pinfunction "2_2") (pintype "passive"))
    )
    (net (code "24") (name "/CB5-1") (class "Default")
      (node (ref "CCB4-1") (pin "1") (pinfunction "1_1") (pintype "passive"))
      (node (ref "CCB5-1") (pin "2") (pinfunction "2_2") (pintype "passive"))
      (node (ref "IC2") (pin "24") (pinfunction "CB5_24") (pintype "bidirectional"))
      (node (ref "R17") (pin "2") (pinfunction "2_2") (pintype "passive"))
      (node (ref "RCB5-1") (pin "2") (pinfunction "2_2") (pintype "passive"))
    )
    (net (code "25") (name "/CB5-IN") (class "Default")
      (node (ref "CBL") (pin "6") (pinfunction "S_6") (pintype "passive"))
      (node (ref "LED6") (pin "1") (pinfunction "A_GREEN_1") (pintype "bidirectional"))
      (node (ref "LED6") (pin "4") (pinfunction "K_RED_4") (pintype "bidirectional"))
      (node (ref "RCB5") (pin "1") (pinfunction "1_1") (pintype "passive"))
    )
    (net (code "26") (name "/CB5-IN-1") (class "Default")
      (node (ref "CBH") (pin "6") (pinfunction "S_6") (pintype "passive"))
      (node (ref "LED17") (pin "1") (pinfunction "A_GREEN_1") (pintype "bidirectional"))
      (node (ref "LED17") (pin "4") (pinfunction "K_RED_4") (pintype "bidirectional"))
      (node (ref "RCB5-1") (pin "1") (pinfunction "1_1") (pintype "passive"))
    )
    (net (code "27") (name "/CB6") (class "Default")
      (node (ref "CCB5") (pin "1") (pinfunction "1_1") (pintype "passive"))
      (node (ref "CCB6") (pin "2") (pinfunction "2_2") (pintype "passive"))
      (node (ref "IC1") (pin "22") (pinfunction "CB6_22") (pintype "bidirectional"))
      (node (ref "R7") (pin "2") (pinfunction "2_2") (pintype "passive"))
      (node (ref "RCB6") (pin "2") (pinfunction "2_2") (pintype "passive"))
    )
    (net (code "28") (name "/CB6-1") (class "Default")
      (node (ref "CCB5-1") (pin "1") (pinfunction "1_1") (pintype "passive"))
      (node (ref "CCB6-1") (pin "2") (pinfunction "2_2") (pintype "passive"))
      (node (ref "IC2") (pin "22") (pinfunction "CB6_22") (pintype "bidirectional"))
      (node (ref "R18") (pin "2") (pinfunction "2_2") (pintype "passive"))
      (node (ref "RCB6-1") (pin "2") (pinfunction "2_2") (pintype "passive"))
    )
    (net (code "29") (name "/CB6-IN") (class "Default")
      (node (ref "CBL") (pin "7") (pinfunction "S_7") (pintype "passive"))
      (node (ref "LED7") (pin "1") (pinfunction "A_GREEN_1") (pintype "bidirectional"))
      (node (ref "LED7") (pin "4") (pinfunction "K_RED_4") (pintype "bidirectional"))
      (node (ref "RCB6") (pin "1") (pinfunction "1_1") (pintype "passive"))
    )
    (net (code "30") (name "/CB6-IN-1") (class "Default")
      (node (ref "CBH") (pin "7") (pinfunction "S_7") (pintype "passive"))
      (node (ref "LED18") (pin "1") (pinfunction "A_GREEN_1") (pintype "bidirectional"))
      (node (ref "LED18") (pin "4") (pinfunction "K_RED_4") (pintype "bidirectional"))
      (node (ref "RCB6-1") (pin "1") (pinfunction "1_1") (pintype "passive"))
    )
    (net (code "31") (name "/CB7") (class "Default")
      (node (ref "CCB6") (pin "1") (pinfunction "1_1") (pintype "passive"))
      (node (ref "CCB7") (pin "2") (pinfunction "2_2") (pintype "passive"))
      (node (ref "IC1") (pin "20") (pinfunction "CB7_20") (pintype "bidirectional"))
      (node (ref "R8") (pin "2") (pinfunction "2_2") (pintype "passive"))
      (node (ref "RCB7") (pin "2") (pinfunction "2_2") (pintype "passive"))
    )
    (net (code "32") (name "/CB7-1") (class "Default")
      (node (ref "CCB6-1") (pin "1") (pinfunction "1_1") (pintype "passive"))
      (node (ref "CCB7-1") (pin "2") (pinfunction "2_2") (pintype "passive"))
      (node (ref "IC2") (pin "20") (pinfunction "CB7_20") (pintype "bidirectional"))
      (node (ref "R19") (pin "2") (pinfunction "2_2") (pintype "passive"))
      (node (ref "RCB7-1") (pin "2") (pinfunction "2_2") (pintype "passive"))
    )
    (net (code "33") (name "/CB7-IN") (class "Default")
      (node (ref "CBL") (pin "8") (pinfunction "S_8") (pintype "passive"))
      (node (ref "LED8") (pin "1") (pinfunction "A_GREEN_1") (pintype "bidirectional"))
      (node (ref "LED8") (pin "4") (pinfunction "K_RED_4") (pintype "bidirectional"))
      (node (ref "RCB7") (pin "1") (pinfunction "1_1") (pintype "passive"))
    )
    (net (code "34") (name "/CB7-IN-1") (class "Default")
      (node (ref "CBH") (pin "8") (pinfunction "S_8") (pintype "passive"))
      (node (ref "LED19") (pin "1") (pinfunction "A_GREEN_1") (pintype "bidirectional"))
      (node (ref "LED19") (pin "4") (pinfunction "K_RED_4") (pintype "bidirectional"))
      (node (ref "RCB7-1") (pin "1") (pinfunction "1_1") (pintype "passive"))
    )
    (net (code "35") (name "/CB8") (class "Default")
      (node (ref "CCB7") (pin "1") (pinfunction "1_1") (pintype "passive"))
      (node (ref "CCB8") (pin "2") (pinfunction "2_2") (pintype "passive"))
      (node (ref "IC1") (pin "18") (pinfunction "CB8_18") (pintype "bidirectional"))
      (node (ref "R9") (pin "2") (pinfunction "2_2") (pintype "passive"))
      (node (ref "RCB8") (pin "2") (pinfunction "2_2") (pintype "passive"))
    )
    (net (code "36") (name "/CB8-1") (class "Default")
      (node (ref "CCB7-1") (pin "1") (pinfunction "1_1") (pintype "passive"))
      (node (ref "CCB8-1") (pin "2") (pinfunction "2_2") (pintype "passive"))
      (node (ref "IC2") (pin "18") (pinfunction "CB8_18") (pintype "bidirectional"))
      (node (ref "R20") (pin "2") (pinfunction "2_2") (pintype "passive"))
      (node (ref "RCB8-1") (pin "2") (pinfunction "2_2") (pintype "passive"))
    )
    (net (code "37") (name "/CB8-IN") (class "Default")
      (node (ref "CBL") (pin "9") (pinfunction "S_9") (pintype "passive"))
      (node (ref "LED9") (pin "1") (pinfunction "A_GREEN_1") (pintype "bidirectional"))
      (node (ref "LED9") (pin "4") (pinfunction "K_RED_4") (pintype "bidirectional"))
      (node (ref "RCB8") (pin "1") (pinfunction "1_1") (pintype "passive"))
    )
    (net (code "38") (name "/CB8-IN-1") (class "Default")
      (node (ref "CBH") (pin "9") (pinfunction "S_9") (pintype "passive"))
      (node (ref "LED20") (pin "1") (pinfunction "A_GREEN_1") (pintype "bidirectional"))
      (node (ref "LED20") (pin "4") (pinfunction "K_RED_4") (pintype "bidirectional"))
      (node (ref "RCB8-1") (pin "1") (pinfunction "1_1") (pintype "passive"))
    )
    (net (code "39") (name "/CB9") (class "Default")
      (node (ref "CCB8") (pin "1") (pinfunction "1_1") (pintype "passive"))
      (node (ref "CCB9") (pin "2") (pinfunction "2_2") (pintype "passive"))
      (node (ref "IC1") (pin "16") (pinfunction "CB9_16") (pintype "bidirectional"))
      (node (ref "R10") (pin "2") (pinfunction "2_2") (pintype "passive"))
      (node (ref "RCB9") (pin "2") (pinfunction "2_2") (pintype "passive"))
    )
    (net (code "40") (name "/CB9-1") (class "Default")
      (node (ref "CCB8-1") (pin "1") (pinfunction "1_1") (pintype "passive"))
      (node (ref "CCB9-1") (pin "2") (pinfunction "2_2") (pintype "passive"))
      (node (ref "IC2") (pin "16") (pinfunction "CB9_16") (pintype "bidirectional"))
      (node (ref "R21") (pin "2") (pinfunction "2_2") (pintype "passive"))
      (node (ref "RCB9-1") (pin "2") (pinfunction "2_2") (pintype "passive"))
    )
    (net (code "41") (name "/CB9-IN") (class "Default")
      (node (ref "CBL") (pin "10") (pinfunction "S_10") (pintype "passive"))
      (node (ref "LED10") (pin "1") (pinfunction "A_GREEN_1") (pintype "bidirectional"))
      (node (ref "LED10") (pin "4") (pinfunction "K_RED_4") (pintype "bidirectional"))
      (node (ref "RCB9") (pin "1") (pinfunction "1_1") (pintype "passive"))
    )
    (net (code "42") (name "/CB9-IN-1") (class "Default")
      (node (ref "CBH") (pin "10") (pinfunction "S_10") (pintype "passive"))
      (node (ref "LED21") (pin "1") (pinfunction "A_GREEN_1") (pintype "bidirectional"))
      (node (ref "LED21") (pin "4") (pinfunction "K_RED_4") (pintype "bidirectional"))
      (node (ref "RCB9-1") (pin "1") (pinfunction "1_1") (pintype "passive"))
    )
    (net (code "43") (name "/CB10") (class "Default")
      (node (ref "CCB10") (pin "1") (pinfunction "1_1") (pintype "passive"))
      (node (ref "CCB9") (pin "1") (pinfunction "1_1") (pintype "passive"))
      (node (ref "IC1") (pin "14") (pinfunction "CB10_14") (pintype "bidirectional"))
      (node (ref "R11") (pin "2") (pinfunction "2_2") (pintype "passive"))
      (node (ref "RCB10") (pin "2") (pinfunction "2_2") (pintype "passive"))
    )
    (net (code "44") (name "/CB10-1") (class "Default")
      (node (ref "CCB10-1") (pin "1") (pinfunction "1_1") (pintype "passive"))
      (node (ref "CCB9-1") (pin "1") (pinfunction "1_1") (pintype "passive"))
      (node (ref "IC2") (pin "14") (pinfunction "CB10_14") (pintype "bidirectional"))
      (node (ref "R22") (pin "2") (pinfunction "2_2") (pintype "passive"))
      (node (ref "RCB10-1") (pin "2") (pinfunction "2_2") (pintype "passive"))
    )
    (net (code "45") (name "/CB10-IN") (class "Default")
      (node (ref "CBL") (pin "11") (pinfunction "S_11") (pintype "passive"))
      (node (ref "LED11") (pin "1") (pinfunction "A_GREEN_1") (pintype "bidirectional"))
      (node (ref "LED11") (pin "4") (pinfunction "K_RED_4") (pintype "bidirectional"))
      (node (ref "RCB10") (pin "1") (pinfunction "1_1") (pintype "passive"))
    )
    (net (code "46") (name "/CB10-IN-1") (class "Default")
      (node (ref "CBH") (pin "11") (pinfunction "S_11") (pintype "passive"))
      (node (ref "LED22") (pin "1") (pinfunction "A_GREEN_1") (pintype "bidirectional"))
      (node (ref "LED22") (pin "4") (pinfunction "K_RED_4") (pintype "bidirectional"))
      (node (ref "RCB10-1") (pin "1") (pinfunction "1_1") (pintype "passive"))
    )
    (net (code "47") (name "/COMHN") (class "Default")
      (node (ref "CCOMHN") (pin "1") (pinfunction "1_1") (pintype "passive"))
      (node (ref "COMH") (pin "1") (pinfunction "S_1") (pintype "passive"))
    )
    (net (code "48") (name "/COMHP") (class "Default")
      (node (ref "CCOMHP") (pin "1") (pinfunction "1_1") (pintype "passive"))
      (node (ref "COMH") (pin "2") (pinfunction "S_2") (pintype "passive"))
    )
    (net (code "49") (name "/COMLN") (class "Default")
      (node (ref "CCOMLN") (pin "1") (pinfunction "1_1") (pintype "passive"))
      (node (ref "COML") (pin "1") (pinfunction "S_1") (pintype "passive"))
    )
    (net (code "50") (name "/COMLP") (class "Default")
      (node (ref "CCOMLP") (pin "1") (pinfunction "1_1") (pintype "passive"))
      (node (ref "COML") (pin "2") (pinfunction "S_2") (pintype "passive"))
    )
    (net (code "51") (name "/COMMN") (class "Default")
      (node (ref "CCOMMN") (pin "1") (pinfunction "1_1") (pintype "passive"))
      (node (ref "RCOMMHN") (pin "1") (pinfunction "1_1") (pintype "passive"))
    )
    (net (code "52") (name "/COMMP") (class "Default")
      (node (ref "CCOMMP") (pin "1") (pinfunction "1_1") (pintype "passive"))
      (node (ref "RCOMMHP") (pin "1") (pinfunction "1_1") (pintype "passive"))
    )
    (net (code "53") (name "/GNDH") (class "Default")
      (node (ref "CAVDD-1") (pin "1") (pinfunction "1_1") (pintype "passive"))
      (node (ref "CBAT-1") (pin "1") (pinfunction "1_1") (pintype "passive"))
      (node (ref "CCOMHNG") (pin "1") (pinfunction "1_1") (pintype "passive"))
      (node (ref "CCOMHPG") (pin "1") (pinfunction "1_1") (pintype "passive"))
      (node (ref "CCOMMHN") (pin "1") (pinfunction "1_1") (pintype "passive"))
      (node (ref "CCOMMHP") (pin "2") (pinfunction "2_2") (pintype "passive"))
      (node (ref "CCVDD-1") (pin "1") (pinfunction "1_1") (pintype "passive"))
      (node (ref "CDVDD-1") (pin "1") (pinfunction "1_1") (pintype "passive"))
      (node (ref "CNEG5V-1") (pin "1") (pinfunction "1_1") (pintype "passive"))
      (node (ref "CNPN1-1") (pin "1") (pinfunction "1_1") (pintype "passive"))
      (node (ref "CNPN2-1") (pin "1") (pinfunction "1_1") (pintype "passive"))
      (node (ref "CREFHP-1") (pin "1") (pinfunction "1_1") (pintype "passive"))
      (node (ref "CTSREF2") (pin "1") (pinfunction "1_1") (pintype "passive"))
      (node (ref "ESDCOMH") (pin "3") (pinfunction "3_3") (pintype "bidirectional"))
      (node (ref "GNDH") (pin "1") (pinfunction "P_1") (pintype "passive"))
      (node (ref "IC2") (pin "36") (pinfunction "REFHM_36") (pintype "bidirectional"))
      (node (ref "IC2") (pin "39") (pinfunction "AVSS_39") (pintype "bidirectional"))
      (node (ref "IC2") (pin "46") (pinfunction "CVSS_46") (pintype "bidirectional"))
      (node (ref "IC2") (pin "50") (pinfunction "DVSS_50") (pintype "bidirectional"))
      (node (ref "IC2") (pin "65") (pinfunction "AVSS?_65") (pintype "bidirectional"))
      (node (ref "RVC0-1") (pin "1") (pinfunction "1_1") (pintype "passive"))
      (node (ref "TEMPH") (pin "10") (pinfunction "S_10") (pintype "passive"))
      (node (ref "TEMPH") (pin "11") (pinfunction "S_11") (pintype "passive"))
      (node (ref "TEMPH") (pin "12") (pinfunction "S_12") (pintype "passive"))
      (node (ref "TEMPH") (pin "13") (pinfunction "S_13") (pintype "passive"))
      (node (ref "TEMPH") (pin "14") (pinfunction "S_14") (pintype "passive"))
      (node (ref "TEMPH") (pin "15") (pinfunction "S_15") (pintype "passive"))
      (node (ref "TEMPH") (pin "16") (pinfunction "S_16") (pintype "passive"))
      (node (ref "TEMPH") (pin "9") (pinfunction "S_9") (pintype "passive"))
      (node (ref "VCH") (pin "1") (pinfunction "S_1") (pintype "passive"))
    )
    (net (code "54") (name "/GNDL") (class "Default")
      (node (ref "CAVDD") (pin "1") (pinfunction "1_1") (pintype "passive"))
      (node (ref "CBAT") (pin "1") (pinfunction "1_1") (pintype "passive"))
      (node (ref "CCOMLNG") (pin "1") (pinfunction "1_1") (pintype "passive"))
      (node (ref "CCOMLPG") (pin "1") (pinfunction "1_1") (pintype "passive"))
      (node (ref "CCOMMLN") (pin "2") (pinfunction "2_2") (pintype "passive"))
      (node (ref "CCOMMLP") (pin "1") (pinfunction "1_1") (pintype "passive"))
      (node (ref "CCVDD") (pin "1") (pinfunction "1_1") (pintype "passive"))
      (node (ref "CDVDD") (pin "1") (pinfunction "1_1") (pintype "passive"))
      (node (ref "CNEG5V") (pin "1") (pinfunction "1_1") (pintype "passive"))
      (node (ref "CNPN1") (pin "1") (pinfunction "1_1") (pintype "passive"))
      (node (ref "CNPN2") (pin "1") (pinfunction "1_1") (pintype "passive"))
      (node (ref "CREFHP") (pin "1") (pinfunction "1_1") (pintype "passive"))
      (node (ref "CTSREF1") (pin "1") (pinfunction "1_1") (pintype "passive"))
      (node (ref "ESDCOML") (pin "3") (pinfunction "3_3") (pintype "bidirectional"))
      (node (ref "GNDL") (pin "1") (pinfunction "P_1") (pintype "passive"))
      (node (ref "IC1") (pin "36") (pinfunction "REFHM_36") (pintype "bidirectional"))
      (node (ref "IC1") (pin "39") (pinfunction "AVSS_39") (pintype "bidirectional"))
      (node (ref "IC1") (pin "46") (pinfunction "CVSS_46") (pintype "bidirectional"))
      (node (ref "IC1") (pin "50") (pinfunction "DVSS_50") (pintype "bidirectional"))
      (node (ref "IC1") (pin "65") (pinfunction "AVSS?_65") (pintype "bidirectional"))
      (node (ref "RVC0") (pin "1") (pinfunction "1_1") (pintype "passive"))
      (node (ref "TEMPL") (pin "10") (pinfunction "S_10") (pintype "passive"))
      (node (ref "TEMPL") (pin "11") (pinfunction "S_11") (pintype "passive"))
      (node (ref "TEMPL") (pin "12") (pinfunction "S_12") (pintype "passive"))
      (node (ref "TEMPL") (pin "13") (pinfunction "S_13") (pintype "passive"))
      (node (ref "TEMPL") (pin "14") (pinfunction "S_14") (pintype "passive"))
      (node (ref "TEMPL") (pin "15") (pinfunction "S_15") (pintype "passive"))
      (node (ref "TEMPL") (pin "16") (pinfunction "S_16") (pintype "passive"))
      (node (ref "TEMPL") (pin "9") (pinfunction "S_9") (pintype "passive"))
      (node (ref "UART") (pin "3") (pinfunction "S_3") (pintype "passive"))
      (node (ref "VCL") (pin "1") (pinfunction "S_1") (pintype "passive"))
    )
    (net (code "55") (name "/LDOIN") (class "Default")
      (node (ref "CNPN2") (pin "2") (pinfunction "2_2") (pintype "passive"))
      (node (ref "IC1") (pin "47") (pinfunction "LDOIN_47") (pintype "bidirectional"))
      (node (ref "T1") (pin "E") (pinfunction "E_E") (pintype "passive"))
    )
    (net (code "56") (name "/LDOIN-1") (class "Default")
      (node (ref "CNPN2-1") (pin "2") (pinfunction "2_2") (pintype "passive"))
      (node (ref "IC2") (pin "47") (pinfunction "LDOIN_47") (pintype "bidirectional"))
      (node (ref "T2") (pin "E") (pinfunction "E_E") (pintype "passive"))
    )
    (net (code "57") (name "/NPNB") (class "Default")
      (node (ref "IC1") (pin "48") (pinfunction "NPNB_48") (pintype "bidirectional"))
      (node (ref "T1") (pin "B") (pinfunction "B_B") (pintype "passive"))
    )
    (net (code "58") (name "/NPNB-1") (class "Default")
      (node (ref "IC2") (pin "48") (pinfunction "NPNB_48") (pintype "bidirectional"))
      (node (ref "T2") (pin "B") (pinfunction "B_B") (pintype "passive"))
    )
    (net (code "59") (name "/TEMP1") (class "Default")
      (node (ref "IC1") (pin "61") (pinfunction "GPIO1_61") (pintype "bidirectional"))
      (node (ref "TEMPL") (pin "1") (pinfunction "S_1") (pintype "passive"))
      (node (ref "TEMPR1") (pin "2") (pinfunction "2_2") (pintype "passive"))
    )
    (net (code "60") (name "/TEMP2") (class "Default")
      (node (ref "IC1") (pin "60") (pinfunction "GPIO2_60") (pintype "bidirectional"))
      (node (ref "TEMPL") (pin "2") (pinfunction "S_2") (pintype "passive"))
      (node (ref "TEMPR2") (pin "2") (pinfunction "2_2") (pintype "passive"))
    )
    (net (code "61") (name "/TEMP3") (class "Default")
      (node (ref "IC1") (pin "59") (pinfunction "GPIO3_59") (pintype "bidirectional"))
      (node (ref "TEMPL") (pin "3") (pinfunction "S_3") (pintype "passive"))
      (node (ref "TEMPR3") (pin "2") (pinfunction "2_2") (pintype "passive"))
    )
    (net (code "62") (name "/TEMP4") (class "Default")
      (node (ref "IC1") (pin "58") (pinfunction "GPIO4_58") (pintype "bidirectional"))
      (node (ref "TEMPL") (pin "4") (pinfunction "S_4") (pintype "passive"))
      (node (ref "TEMPR4") (pin "2") (pinfunction "2_2") (pintype "passive"))
    )
    (net (code "63") (name "/TEMP5") (class "Default")
      (node (ref "IC1") (pin "57") (pinfunction "GPIO5_57") (pintype "bidirectional"))
      (node (ref "TEMPL") (pin "5") (pinfunction "S_5") (pintype "passive"))
      (node (ref "TEMPR5") (pin "2") (pinfunction "2_2") (pintype "passive"))
    )
    (net (code "64") (name "/TEMP6") (class "Default")
      (node (ref "IC1") (pin "56") (pinfunction "GPIO6_56") (pintype "bidirectional"))
      (node (ref "TEMPL") (pin "6") (pinfunction "S_6") (pintype "passive"))
      (node (ref "TEMPR6") (pin "2") (pinfunction "2_2") (pintype "passive"))
    )
    (net (code "65") (name "/TEMP7") (class "Default")
      (node (ref "IC1") (pin "55") (pinfunction "GPIO7_55") (pintype "bidirectional"))
      (node (ref "TEMPL") (pin "7") (pinfunction "S_7") (pintype "passive"))
      (node (ref "TEMPR7") (pin "2") (pinfunction "2_2") (pintype "passive"))
    )
    (net (code "66") (name "/TEMP8") (class "Default")
      (node (ref "IC1") (pin "54") (pinfunction "GPIO8_54") (pintype "bidirectional"))
      (node (ref "TEMPL") (pin "8") (pinfunction "S_8") (pintype "passive"))
      (node (ref "TEMPR8") (pin "2") (pinfunction "2_2") (pintype "passive"))
    )
    (net (code "67") (name "/TEMP9") (class "Default")
      (node (ref "IC2") (pin "61") (pinfunction "GPIO1_61") (pintype "bidirectional"))
      (node (ref "TEMPH") (pin "1") (pinfunction "S_1") (pintype "passive"))
      (node (ref "TEMPR9") (pin "2") (pinfunction "2_2") (pintype "passive"))
    )
    (net (code "68") (name "/TEMP10") (class "Default")
      (node (ref "IC2") (pin "60") (pinfunction "GPIO2_60") (pintype "bidirectional"))
      (node (ref "TEMPH") (pin "2") (pinfunction "S_2") (pintype "passive"))
      (node (ref "TEMPR10") (pin "2") (pinfunction "2_2") (pintype "passive"))
    )
    (net (code "69") (name "/TEMP11") (class "Default")
      (node (ref "IC2") (pin "59") (pinfunction "GPIO3_59") (pintype "bidirectional"))
      (node (ref "TEMPH") (pin "3") (pinfunction "S_3") (pintype "passive"))
      (node (ref "TEMPR11") (pin "2") (pinfunction "2_2") (pintype "passive"))
    )
    (net (code "70") (name "/TEMP12") (class "Default")
      (node (ref "IC2") (pin "58") (pinfunction "GPIO4_58") (pintype "bidirectional"))
      (node (ref "TEMPH") (pin "4") (pinfunction "S_4") (pintype "passive"))
      (node (ref "TEMPR12") (pin "2") (pinfunction "2_2") (pintype "passive"))
    )
    (net (code "71") (name "/TEMP13") (class "Default")
      (node (ref "IC2") (pin "57") (pinfunction "GPIO5_57") (pintype "bidirectional"))
      (node (ref "TEMPH") (pin "5") (pinfunction "S_5") (pintype "passive"))
      (node (ref "TEMPR13") (pin "2") (pinfunction "2_2") (pintype "passive"))
    )
    (net (code "72") (name "/TEMP14") (class "Default")
      (node (ref "IC2") (pin "56") (pinfunction "GPIO6_56") (pintype "bidirectional"))
      (node (ref "TEMPH") (pin "6") (pinfunction "S_6") (pintype "passive"))
      (node (ref "TEMPR14") (pin "2") (pinfunction "2_2") (pintype "passive"))
    )
    (net (code "73") (name "/TEMP15") (class "Default")
      (node (ref "IC2") (pin "55") (pinfunction "GPIO7_55") (pintype "bidirectional"))
      (node (ref "TEMPH") (pin "7") (pinfunction "S_7") (pintype "passive"))
      (node (ref "TEMPR15") (pin "2") (pinfunction "2_2") (pintype "passive"))
    )
    (net (code "74") (name "/TEMP16") (class "Default")
      (node (ref "IC2") (pin "54") (pinfunction "GPIO8_54") (pintype "bidirectional"))
      (node (ref "TEMPH") (pin "8") (pinfunction "S_8") (pintype "passive"))
      (node (ref "TEMPR16") (pin "2") (pinfunction "2_2") (pintype "passive"))
    )
    (net (code "75") (name "/TSREF") (class "Default")
      (node (ref "CTSREF1") (pin "2") (pinfunction "2_2") (pintype "passive"))
      (node (ref "IC1") (pin "51") (pinfunction "TSREF_51") (pintype "bidirectional"))
      (node (ref "TEMPR1") (pin "1") (pinfunction "1_1") (pintype "passive"))
      (node (ref "TEMPR2") (pin "1") (pinfunction "1_1") (pintype "passive"))
      (node (ref "TEMPR3") (pin "1") (pinfunction "1_1") (pintype "passive"))
      (node (ref "TEMPR4") (pin "1") (pinfunction "1_1") (pintype "passive"))
      (node (ref "TEMPR5") (pin "1") (pinfunction "1_1") (pintype "passive"))
      (node (ref "TEMPR6") (pin "1") (pinfunction "1_1") (pintype "passive"))
      (node (ref "TEMPR7") (pin "1") (pinfunction "1_1") (pintype "passive"))
      (node (ref "TEMPR8") (pin "1") (pinfunction "1_1") (pintype "passive"))
    )
    (net (code "76") (name "/TSREF-1") (class "Default")
      (node (ref "CTSREF2") (pin "2") (pinfunction "2_2") (pintype "passive"))
      (node (ref "IC2") (pin "51") (pinfunction "TSREF_51") (pintype "bidirectional"))
      (node (ref "TEMPR10") (pin "1") (pinfunction "1_1") (pintype "passive"))
      (node (ref "TEMPR11") (pin "1") (pinfunction "1_1") (pintype "passive"))
      (node (ref "TEMPR12") (pin "1") (pinfunction "1_1") (pintype "passive"))
      (node (ref "TEMPR13") (pin "1") (pinfunction "1_1") (pintype "passive"))
      (node (ref "TEMPR14") (pin "1") (pinfunction "1_1") (pintype "passive"))
      (node (ref "TEMPR15") (pin "1") (pinfunction "1_1") (pintype "passive"))
      (node (ref "TEMPR16") (pin "1") (pinfunction "1_1") (pintype "passive"))
      (node (ref "TEMPR9") (pin "1") (pinfunction "1_1") (pintype "passive"))
    )
    (net (code "77") (name "/VC0") (class "Default")
      (node (ref "CVC0") (pin "2") (pinfunction "2_2") (pintype "passive"))
      (node (ref "IC1") (pin "35") (pinfunction "VC0_35") (pintype "bidirectional"))
      (node (ref "RVC0") (pin "2") (pinfunction "2_2") (pintype "passive"))
    )
    (net (code "78") (name "/VC0-1") (class "Default")
      (node (ref "CVC0-1") (pin "2") (pinfunction "2_2") (pintype "passive"))
      (node (ref "IC2") (pin "35") (pinfunction "VC0_35") (pintype "bidirectional"))
      (node (ref "RVC0-1") (pin "2") (pinfunction "2_2") (pintype "passive"))
    )
    (net (code "79") (name "/VC1") (class "Default")
      (node (ref "CVC0") (pin "1") (pinfunction "1_1") (pintype "passive"))
      (node (ref "CVC1") (pin "2") (pinfunction "2_2") (pintype "passive"))
      (node (ref "IC1") (pin "33") (pinfunction "VC1_33") (pintype "bidirectional"))
      (node (ref "RVC1") (pin "2") (pinfunction "2_2") (pintype "passive"))
    )
    (net (code "80") (name "/VC1-1") (class "Default")
      (node (ref "CVC0-1") (pin "1") (pinfunction "1_1") (pintype "passive"))
      (node (ref "CVC1-1") (pin "2") (pinfunction "2_2") (pintype "passive"))
      (node (ref "IC2") (pin "33") (pinfunction "VC1_33") (pintype "bidirectional"))
      (node (ref "RVC1-1") (pin "2") (pinfunction "2_2") (pintype "passive"))
    )
    (net (code "81") (name "/VC1-IN") (class "Default")
      (node (ref "RVC1") (pin "1") (pinfunction "1_1") (pintype "passive"))
      (node (ref "VCL") (pin "2") (pinfunction "S_2") (pintype "passive"))
    )
    (net (code "82") (name "/VC1-IN-1") (class "Default")
      (node (ref "RVC1-1") (pin "1") (pinfunction "1_1") (pintype "passive"))
      (node (ref "VCH") (pin "2") (pinfunction "S_2") (pintype "passive"))
    )
    (net (code "83") (name "/VC2") (class "Default")
      (node (ref "CVC1") (pin "1") (pinfunction "1_1") (pintype "passive"))
      (node (ref "CVC2") (pin "2") (pinfunction "2_2") (pintype "passive"))
      (node (ref "IC1") (pin "31") (pinfunction "VC2_31") (pintype "bidirectional"))
      (node (ref "RVC2") (pin "2") (pinfunction "2_2") (pintype "passive"))
    )
    (net (code "84") (name "/VC2-1") (class "Default")
      (node (ref "CVC1-1") (pin "1") (pinfunction "1_1") (pintype "passive"))
      (node (ref "CVC2-1") (pin "2") (pinfunction "2_2") (pintype "passive"))
      (node (ref "IC2") (pin "31") (pinfunction "VC2_31") (pintype "bidirectional"))
      (node (ref "RVC2-1") (pin "2") (pinfunction "2_2") (pintype "passive"))
    )
    (net (code "85") (name "/VC2-IN") (class "Default")
      (node (ref "RVC2") (pin "1") (pinfunction "1_1") (pintype "passive"))
      (node (ref "VCL") (pin "3") (pinfunction "S_3") (pintype "passive"))
    )
    (net (code "86") (name "/VC2-IN-1") (class "Default")
      (node (ref "RVC2-1") (pin "1") (pinfunction "1_1") (pintype "passive"))
      (node (ref "VCH") (pin "3") (pinfunction "S_3") (pintype "passive"))
    )
    (net (code "87") (name "/VC3") (class "Default")
      (node (ref "CVC2") (pin "1") (pinfunction "1_1") (pintype "passive"))
      (node (ref "CVC3") (pin "2") (pinfunction "2_2") (pintype "passive"))
      (node (ref "IC1") (pin "29") (pinfunction "VC3_29") (pintype "bidirectional"))
      (node (ref "RVC3") (pin "2") (pinfunction "2_2") (pintype "passive"))
    )
    (net (code "88") (name "/VC3-1") (class "Default")
      (node (ref "CVC2-1") (pin "1") (pinfunction "1_1") (pintype "passive"))
      (node (ref "CVC3-1") (pin "2") (pinfunction "2_2") (pintype "passive"))
      (node (ref "IC2") (pin "29") (pinfunction "VC3_29") (pintype "bidirectional"))
      (node (ref "RVC3-1") (pin "2") (pinfunction "2_2") (pintype "passive"))
    )
    (net (code "89") (name "/VC3-IN") (class "Default")
      (node (ref "RVC3") (pin "1") (pinfunction "1_1") (pintype "passive"))
      (node (ref "VCL") (pin "4") (pinfunction "S_4") (pintype "passive"))
    )
    (net (code "90") (name "/VC3-IN-1") (class "Default")
      (node (ref "RVC3-1") (pin "1") (pinfunction "1_1") (pintype "passive"))
      (node (ref "VCH") (pin "4") (pinfunction "S_4") (pintype "passive"))
    )
    (net (code "91") (name "/VC4") (class "Default")
      (node (ref "CVC3") (pin "1") (pinfunction "1_1") (pintype "passive"))
      (node (ref "CVC4") (pin "2") (pinfunction "2_2") (pintype "passive"))
      (node (ref "IC1") (pin "27") (pinfunction "VC4_27") (pintype "bidirectional"))
      (node (ref "RVC4") (pin "2") (pinfunction "2_2") (pintype "passive"))
    )
    (net (code "92") (name "/VC4-1") (class "Default")
      (node (ref "CVC3-1") (pin "1") (pinfunction "1_1") (pintype "passive"))
      (node (ref "CVC4-1") (pin "2") (pinfunction "2_2") (pintype "passive"))
      (node (ref "IC2") (pin "27") (pinfunction "VC4_27") (pintype "bidirectional"))
      (node (ref "RVC4-1") (pin "2") (pinfunction "2_2") (pintype "passive"))
    )
    (net (code "93") (name "/VC4-IN") (class "Default")
      (node (ref "RVC4") (pin "1") (pinfunction "1_1") (pintype "passive"))
      (node (ref "VCL") (pin "5") (pinfunction "S_5") (pintype "passive"))
    )
    (net (code "94") (name "/VC4-IN-1") (class "Default")
      (node (ref "RVC4-1") (pin "1") (pinfunction "1_1") (pintype "passive"))
      (node (ref "VCH") (pin "5") (pinfunction "S_5") (pintype "passive"))
    )
    (net (code "95") (name "/VC5") (class "Default")
      (node (ref "CVC4") (pin "1") (pinfunction "1_1") (pintype "passive"))
      (node (ref "CVC5") (pin "2") (pinfunction "2_2") (pintype "passive"))
      (node (ref "IC1") (pin "25") (pinfunction "VC5_25") (pintype "bidirectional"))
      (node (ref "RVC5") (pin "2") (pinfunction "2_2") (pintype "passive"))
    )
    (net (code "96") (name "/VC5-1") (class "Default")
      (node (ref "CVC4-1") (pin "1") (pinfunction "1_1") (pintype "passive"))
      (node (ref "CVC5-1") (pin "2") (pinfunction "2_2") (pintype "passive"))
      (node (ref "IC2") (pin "25") (pinfunction "VC5_25") (pintype "bidirectional"))
      (node (ref "RVC5-1") (pin "2") (pinfunction "2_2") (pintype "passive"))
    )
    (net (code "97") (name "/VC5-IN") (class "Default")
      (node (ref "RVC5") (pin "1") (pinfunction "1_1") (pintype "passive"))
      (node (ref "VCL") (pin "6") (pinfunction "S_6") (pintype "passive"))
    )
    (net (code "98") (name "/VC5-IN-1") (class "Default")
      (node (ref "RVC5-1") (pin "1") (pinfunction "1_1") (pintype "passive"))
      (node (ref "VCH") (pin "6") (pinfunction "S_6") (pintype "passive"))
    )
    (net (code "99") (name "/VC6") (class "Default")
      (node (ref "CVC5") (pin "1") (pinfunction "1_1") (pintype "passive"))
      (node (ref "CVC6") (pin "2") (pinfunction "2_2") (pintype "passive"))
      (node (ref "IC1") (pin "23") (pinfunction "VC6_23") (pintype "bidirectional"))
      (node (ref "RVC6") (pin "2") (pinfunction "2_2") (pintype "passive"))
    )
    (net (code "100") (name "/VC6-1") (class "Default")
      (node (ref "CVC5-1") (pin "1") (pinfunction "1_1") (pintype "passive"))
      (node (ref "CVC6-1") (pin "2") (pinfunction "2_2") (pintype "passive"))
      (node (ref "IC2") (pin "23") (pinfunction "VC6_23") (pintype "bidirectional"))
      (node (ref "RVC6-1") (pin "2") (pinfunction "2_2") (pintype "passive"))
    )
    (net (code "101") (name "/VC6-IN") (class "Default")
      (node (ref "RVC6") (pin "1") (pinfunction "1_1") (pintype "passive"))
      (node (ref "VCL") (pin "7") (pinfunction "S_7") (pintype "passive"))
    )
    (net (code "102") (name "/VC6-IN-1") (class "Default")
      (node (ref "RVC6-1") (pin "1") (pinfunction "1_1") (pintype "passive"))
      (node (ref "VCH") (pin "7") (pinfunction "S_7") (pintype "passive"))
    )
    (net (code "103") (name "/VC7") (class "Default")
      (node (ref "CVC6") (pin "1") (pinfunction "1_1") (pintype "passive"))
      (node (ref "CVC7") (pin "2") (pinfunction "2_2") (pintype "passive"))
      (node (ref "IC1") (pin "21") (pinfunction "VC7_21") (pintype "bidirectional"))
      (node (ref "RVC7") (pin "2") (pinfunction "2_2") (pintype "passive"))
    )
    (net (code "104") (name "/VC7-1") (class "Default")
      (node (ref "CVC6-1") (pin "1") (pinfunction "1_1") (pintype "passive"))
      (node (ref "CVC7-1") (pin "2") (pinfunction "2_2") (pintype "passive"))
      (node (ref "IC2") (pin "21") (pinfunction "VC7_21") (pintype "bidirectional"))
      (node (ref "RVC7-1") (pin "2") (pinfunction "2_2") (pintype "passive"))
    )
    (net (code "105") (name "/VC7-IN") (class "Default")
      (node (ref "RVC7") (pin "1") (pinfunction "1_1") (pintype "passive"))
      (node (ref "VCL") (pin "8") (pinfunction "S_8") (pintype "passive"))
    )
    (net (code "106") (name "/VC7-IN-1") (class "Default")
      (node (ref "RVC7-1") (pin "1") (pinfunction "1_1") (pintype "passive"))
      (node (ref "VCH") (pin "8") (pinfunction "S_8") (pintype "passive"))
    )
    (net (code "107") (name "/VC8") (class "Default")
      (node (ref "CVC7") (pin "1") (pinfunction "1_1") (pintype "passive"))
      (node (ref "CVC8") (pin "2") (pinfunction "2_2") (pintype "passive"))
      (node (ref "IC1") (pin "19") (pinfunction "VC8_19") (pintype "bidirectional"))
      (node (ref "RVC8") (pin "2") (pinfunction "2_2") (pintype "passive"))
    )
    (net (code "108") (name "/VC8-1") (class "Default")
      (node (ref "CVC7-1") (pin "1") (pinfunction "1_1") (pintype "passive"))
      (node (ref "CVC8-1") (pin "2") (pinfunction "2_2") (pintype "passive"))
      (node (ref "IC2") (pin "19") (pinfunction "VC8_19") (pintype "bidirectional"))
      (node (ref "RVC8-1") (pin "2") (pinfunction "2_2") (pintype "passive"))
    )
    (net (code "109") (name "/VC8-IN") (class "Default")
      (node (ref "RVC8") (pin "1") (pinfunction "1_1") (pintype "passive"))
      (node (ref "VCL") (pin "9") (pinfunction "S_9") (pintype "passive"))
    )
    (net (code "110") (name "/VC8-IN-1") (class "Default")
      (node (ref "RVC8-1") (pin "1") (pinfunction "1_1") (pintype "passive"))
      (node (ref "VCH") (pin "9") (pinfunction "S_9") (pintype "passive"))
    )
    (net (code "111") (name "/VC9") (class "Default")
      (node (ref "CVC8") (pin "1") (pinfunction "1_1") (pintype "passive"))
      (node (ref "CVC9") (pin "2") (pinfunction "2_2") (pintype "passive"))
      (node (ref "IC1") (pin "17") (pinfunction "VC9_17") (pintype "bidirectional"))
      (node (ref "RVC9") (pin "2") (pinfunction "2_2") (pintype "passive"))
    )
    (net (code "112") (name "/VC9-1") (class "Default")
      (node (ref "CVC8-1") (pin "1") (pinfunction "1_1") (pintype "passive"))
      (node (ref "CVC9-1") (pin "2") (pinfunction "2_2") (pintype "passive"))
      (node (ref "IC2") (pin "17") (pinfunction "VC9_17") (pintype "bidirectional"))
      (node (ref "RVC9-1") (pin "2") (pinfunction "2_2") (pintype "passive"))
    )
    (net (code "113") (name "/VC9-IN") (class "Default")
      (node (ref "RVC9") (pin "1") (pinfunction "1_1") (pintype "passive"))
      (node (ref "VCL") (pin "10") (pinfunction "S_10") (pintype "passive"))
    )
    (net (code "114") (name "/VC9-IN-1") (class "Default")
      (node (ref "RVC9-1") (pin "1") (pinfunction "1_1") (pintype "passive"))
      (node (ref "VCH") (pin "10") (pinfunction "S_10") (pintype "passive"))
    )
    (net (code "115") (name "/VC10") (class "Default")
      (node (ref "CVC9") (pin "1") (pinfunction "1_1") (pintype "passive"))
      (node (ref "IC1") (pin "15") (pinfunction "VC10_15") (pintype "bidirectional"))
      (node (ref "RVC10") (pin "2") (pinfunction "2_2") (pintype "passive"))
    )
    (net (code "116") (name "/VC10-1") (class "Default")
      (node (ref "CVC9-1") (pin "1") (pinfunction "1_1") (pintype "passive"))
      (node (ref "IC2") (pin "15") (pinfunction "VC10_15") (pintype "bidirectional"))
      (node (ref "RVC10-1") (pin "2") (pinfunction "2_2") (pintype "passive"))
    )
    (net (code "117") (name "/VC_CB_HIGH") (class "Default")
      (node (ref "CBAT") (pin "2") (pinfunction "2_2") (pintype "passive"))
      (node (ref "CCB10") (pin "2") (pinfunction "2_2") (pintype "passive"))
      (node (ref "IC1") (pin "1") (pinfunction "BAT_1") (pintype "bidirectional"))
      (node (ref "IC1") (pin "10") (pinfunction "CB12_10") (pintype "bidirectional"))
      (node (ref "IC1") (pin "11") (pinfunction "VC12_11") (pintype "bidirectional"))
      (node (ref "IC1") (pin "12") (pinfunction "CB11_12") (pintype "bidirectional"))
      (node (ref "IC1") (pin "13") (pinfunction "VC11_13") (pintype "bidirectional"))
      (node (ref "IC1") (pin "2") (pinfunction "CB16_2") (pintype "bidirectional"))
      (node (ref "IC1") (pin "3") (pinfunction "VC16_3") (pintype "bidirectional"))
      (node (ref "IC1") (pin "4") (pinfunction "CB15_4") (pintype "bidirectional"))
      (node (ref "IC1") (pin "5") (pinfunction "VC15_5") (pintype "bidirectional"))
      (node (ref "IC1") (pin "6") (pinfunction "CB14_6") (pintype "bidirectional"))
      (node (ref "IC1") (pin "7") (pinfunction "VC14_7") (pintype "bidirectional"))
      (node (ref "IC1") (pin "8") (pinfunction "CB13_8") (pintype "bidirectional"))
      (node (ref "IC1") (pin "9") (pinfunction "VC13_9") (pintype "bidirectional"))
      (node (ref "RBAT") (pin "1") (pinfunction "1_1") (pintype "passive"))
    )
    (net (code "118") (name "/VC_CB_HIGH-1") (class "Default")
      (node (ref "CBAT-1") (pin "2") (pinfunction "2_2") (pintype "passive"))
      (node (ref "CCB10-1") (pin "2") (pinfunction "2_2") (pintype "passive"))
      (node (ref "IC2") (pin "1") (pinfunction "BAT_1") (pintype "bidirectional"))
      (node (ref "IC2") (pin "10") (pinfunction "CB12_10") (pintype "bidirectional"))
      (node (ref "IC2") (pin "11") (pinfunction "VC12_11") (pintype "bidirectional"))
      (node (ref "IC2") (pin "12") (pinfunction "CB11_12") (pintype "bidirectional"))
      (node (ref "IC2") (pin "13") (pinfunction "VC11_13") (pintype "bidirectional"))
      (node (ref "IC2") (pin "2") (pinfunction "CB16_2") (pintype "bidirectional"))
      (node (ref "IC2") (pin "3") (pinfunction "VC16_3") (pintype "bidirectional"))
      (node (ref "IC2") (pin "4") (pinfunction "CB15_4") (pintype "bidirectional"))
      (node (ref "IC2") (pin "5") (pinfunction "VC15_5") (pintype "bidirectional"))
      (node (ref "IC2") (pin "6") (pinfunction "CB14_6") (pintype "bidirectional"))
      (node (ref "IC2") (pin "7") (pinfunction "VC14_7") (pintype "bidirectional"))
      (node (ref "IC2") (pin "8") (pinfunction "CB13_8") (pintype "bidirectional"))
      (node (ref "IC2") (pin "9") (pinfunction "VC13_9") (pintype "bidirectional"))
      (node (ref "RBAT-1") (pin "1") (pinfunction "1_1") (pintype "passive"))
    )
    (net (code "119") (name "Net-(CCOMHN-Pad2)") (class "Default")
      (node (ref "CCOMHN") (pin "2") (pinfunction "2_2") (pintype "passive"))
      (node (ref "ESDCOMH") (pin "2") (pinfunction "2_2") (pintype "bidirectional"))
      (node (ref "RCOMHN") (pin "1") (pinfunction "1_1") (pintype "passive"))
    )
    (net (code "120") (name "Net-(CCOMHP-Pad2)") (class "Default")
      (node (ref "CCOMHP") (pin "2") (pinfunction "2_2") (pintype "passive"))
      (node (ref "ESDCOMH") (pin "1") (pinfunction "1_1") (pintype "bidirectional"))
      (node (ref "RCOMHP") (pin "1") (pinfunction "1_1") (pintype "passive"))
    )
    (net (code "121") (name "Net-(CCOMLN-Pad2)") (class "Default")
      (node (ref "CCOMLN") (pin "2") (pinfunction "2_2") (pintype "passive"))
      (node (ref "ESDCOML") (pin "1") (pinfunction "1_1") (pintype "bidirectional"))
      (node (ref "RCOMLN") (pin "1") (pinfunction "1_1") (pintype "passive"))
    )
    (net (code "122") (name "Net-(CCOMLP-Pad2)") (class "Default")
      (node (ref "CCOMLP") (pin "2") (pinfunction "2_2") (pintype "passive"))
      (node (ref "ESDCOML") (pin "2") (pinfunction "2_2") (pintype "bidirectional"))
      (node (ref "RCOMLP") (pin "1") (pinfunction "1_1") (pintype "passive"))
    )
    (net (code "123") (name "Net-(CCOMMN-Pad2)") (class "Default")
      (node (ref "CCOMMN") (pin "2") (pinfunction "2_2") (pintype "passive"))
      (node (ref "RCOMMLN") (pin "1") (pinfunction "1_1") (pintype "passive"))
    )
    (net (code "124") (name "Net-(CCOMMP-Pad2)") (class "Default")
      (node (ref "CCOMMP") (pin "2") (pinfunction "2_2") (pintype "passive"))
      (node (ref "RCOMMLP") (pin "1") (pinfunction "1_1") (pintype "passive"))
    )
    (net (code "125") (name "Net-(CNPN1-1-Pad2)") (class "Default")
      (node (ref "CNPN1-1") (pin "2") (pinfunction "2_2") (pintype "passive"))
      (node (ref "RNPN-1") (pin "1") (pinfunction "1_1") (pintype "passive"))
      (node (ref "T2") (pin "C") (pinfunction "C_C") (pintype "passive"))
    )
    (net (code "126") (name "Net-(CNPN1-Pad2)") (class "Default")
      (node (ref "CNPN1") (pin "2") (pinfunction "2_2") (pintype "passive"))
      (node (ref "RNPN") (pin "1") (pinfunction "1_1") (pintype "passive"))
      (node (ref "T1") (pin "C") (pinfunction "C_C") (pintype "passive"))
    )
    (net (code "127") (name "Net-(IC1-AVDD)") (class "Default")
      (node (ref "CAVDD") (pin "2") (pinfunction "2_2") (pintype "passive"))
      (node (ref "IC1") (pin "38") (pinfunction "AVDD_38") (pintype "bidirectional"))
    )
    (net (code "128") (name "Net-(IC1-BBN(SRN))") (class "Default")
      (node (ref "CCS") (pin "1") (pinfunction "1_1") (pintype "passive"))
      (node (ref "IC1") (pin "63") (pinfunction "BBN(SRN)_63") (pintype "bidirectional"))
      (node (ref "RCS2") (pin "2") (pinfunction "2_2") (pintype "passive"))
    )
    (net (code "129") (name "Net-(IC1-BBP(SRP))") (class "Default")
      (node (ref "CCS") (pin "2") (pinfunction "2_2") (pintype "passive"))
      (node (ref "IC1") (pin "64") (pinfunction "BBP(SRP)_64") (pintype "bidirectional"))
      (node (ref "RCS1") (pin "2") (pinfunction "2_2") (pintype "passive"))
    )
    (net (code "130") (name "Net-(IC1-COMHN)") (class "Default")
      (node (ref "CCOMMLN") (pin "1") (pinfunction "1_1") (pintype "passive"))
      (node (ref "IC1") (pin "42") (pinfunction "COMHN_42") (pintype "bidirectional"))
      (node (ref "RCOMML") (pin "2") (pinfunction "2_2") (pintype "passive"))
      (node (ref "RCOMMLN") (pin "2") (pinfunction "2_2") (pintype "passive"))
    )
    (net (code "131") (name "Net-(IC1-COMHP)") (class "Default")
      (node (ref "CCOMMLP") (pin "2") (pinfunction "2_2") (pintype "passive"))
      (node (ref "IC1") (pin "43") (pinfunction "COMHP_43") (pintype "bidirectional"))
      (node (ref "RCOMML") (pin "1") (pinfunction "1_1") (pintype "passive"))
      (node (ref "RCOMMLP") (pin "2") (pinfunction "2_2") (pintype "passive"))
    )
    (net (code "132") (name "Net-(IC1-COMLN)") (class "Default")
      (node (ref "CCOMLNG") (pin "2") (pinfunction "2_2") (pintype "passive"))
      (node (ref "IC1") (pin "41") (pinfunction "COMLN_41") (pintype "bidirectional"))
      (node (ref "RCOML") (pin "1") (pinfunction "1_1") (pintype "passive"))
      (node (ref "RCOMLN") (pin "2") (pinfunction "2_2") (pintype "passive"))
    )
    (net (code "133") (name "Net-(IC1-COMLP)") (class "Default")
      (node (ref "CCOMLPG") (pin "2") (pinfunction "2_2") (pintype "passive"))
      (node (ref "IC1") (pin "40") (pinfunction "COMLP_40") (pintype "bidirectional"))
      (node (ref "RCOML") (pin "2") (pinfunction "2_2") (pintype "passive"))
      (node (ref "RCOMLP") (pin "2") (pinfunction "2_2") (pintype "passive"))
    )
    (net (code "134") (name "Net-(IC1-CVDD)") (class "Default")
      (node (ref "CCVDD") (pin "2") (pinfunction "2_2") (pintype "passive"))
      (node (ref "DISABLE_UART") (pin "1") (pinfunction "1_1") (pintype "passive"))
      (node (ref "IC1") (pin "45") (pinfunction "CVDD_45") (pintype "bidirectional"))
    )
    (net (code "135") (name "Net-(IC1-DVDD)") (class "Default")
      (node (ref "CDVDD") (pin "2") (pinfunction "2_2") (pintype "passive"))
      (node (ref "IC1") (pin "49") (pinfunction "DVDD_49") (pintype "bidirectional"))
    )
    (net (code "136") (name "Net-(IC1-NEG5V)") (class "Default")
      (node (ref "CNEG5V") (pin "2") (pinfunction "2_2") (pintype "passive"))
      (node (ref "IC1") (pin "44") (pinfunction "NEG5V_44") (pintype "bidirectional"))
    )
    (net (code "137") (name "Net-(IC1-NFAULT)") (class "Default")
      (node (ref "IC1") (pin "62") (pinfunction "NFAULT_62") (pintype "bidirectional"))
      (node (ref "NFAULT") (pin "TP") (pinfunction "TP_TP") (pintype "input"))
    )
    (net (code "138") (name "Net-(IC1-REFHP)") (class "Default")
      (node (ref "CREFHP") (pin "2") (pinfunction "2_2") (pintype "passive"))
      (node (ref "IC1") (pin "37") (pinfunction "REFHP_37") (pintype "bidirectional"))
    )
    (net (code "139") (name "Net-(IC1-RX)") (class "Default")
      (node (ref "DISABLE_UART") (pin "2") (pinfunction "2_2") (pintype "passive"))
      (node (ref "IC1") (pin "52") (pinfunction "RX_52") (pintype "bidirectional"))
      (node (ref "UART") (pin "2") (pinfunction "S_2") (pintype "passive"))
    )
    (net (code "140") (name "Net-(IC1-TX)") (class "Default")
      (node (ref "IC1") (pin "53") (pinfunction "TX_53") (pintype "bidirectional"))
      (node (ref "UART") (pin "1") (pinfunction "S_1") (pintype "passive"))
    )
    (net (code "141") (name "Net-(IC2-AVDD)") (class "Default")
      (node (ref "CAVDD-1") (pin "2") (pinfunction "2_2") (pintype "passive"))
      (node (ref "IC2") (pin "38") (pinfunction "AVDD_38") (pintype "bidirectional"))
    )
    (net (code "142") (name "Net-(IC2-COMHN)") (class "Default")
      (node (ref "CCOMHNG") (pin "2") (pinfunction "2_2") (pintype "passive"))
      (node (ref "IC2") (pin "42") (pinfunction "COMHN_42") (pintype "bidirectional"))
      (node (ref "RCOMH") (pin "2") (pinfunction "2_2") (pintype "passive"))
      (node (ref "RCOMHN") (pin "2") (pinfunction "2_2") (pintype "passive"))
    )
    (net (code "143") (name "Net-(IC2-COMHP)") (class "Default")
      (node (ref "CCOMHPG") (pin "2") (pinfunction "2_2") (pintype "passive"))
      (node (ref "IC2") (pin "43") (pinfunction "COMHP_43") (pintype "bidirectional"))
      (node (ref "RCOMH") (pin "1") (pinfunction "1_1") (pintype "passive"))
      (node (ref "RCOMHP") (pin "2") (pinfunction "2_2") (pintype "passive"))
    )
    (net (code "144") (name "Net-(IC2-COMLN)") (class "Default")
      (node (ref "CCOMMHN") (pin "2") (pinfunction "2_2") (pintype "passive"))
      (node (ref "IC2") (pin "41") (pinfunction "COMLN_41") (pintype "bidirectional"))
      (node (ref "RCOMMH") (pin "1") (pinfunction "1_1") (pintype "passive"))
      (node (ref "RCOMMHN") (pin "2") (pinfunction "2_2") (pintype "passive"))
    )
    (net (code "145") (name "Net-(IC2-COMLP)") (class "Default")
      (node (ref "CCOMMHP") (pin "1") (pinfunction "1_1") (pintype "passive"))
      (node (ref "IC2") (pin "40") (pinfunction "COMLP_40") (pintype "bidirectional"))
      (node (ref "RCOMMH") (pin "2") (pinfunction "2_2") (pintype "passive"))
      (node (ref "RCOMMHP") (pin "2") (pinfunction "2_2") (pintype "passive"))
    )
    (net (code "146") (name "Net-(IC2-CVDD)") (class "Default")
      (node (ref "CCVDD-1") (pin "2") (pinfunction "2_2") (pintype "passive"))
      (node (ref "IC2") (pin "45") (pinfunction "CVDD_45") (pintype "bidirectional"))
      (node (ref "IC2") (pin "52") (pinfunction "RX_52") (pintype "bidirectional"))
    )
    (net (code "147") (name "Net-(IC2-DVDD)") (class "Default")
      (node (ref "CDVDD-1") (pin "2") (pinfunction "2_2") (pintype "passive"))
      (node (ref "IC2") (pin "49") (pinfunction "DVDD_49") (pintype "bidirectional"))
    )
    (net (code "148") (name "Net-(IC2-NEG5V)") (class "Default")
      (node (ref "CNEG5V-1") (pin "2") (pinfunction "2_2") (pintype "passive"))
      (node (ref "IC2") (pin "44") (pinfunction "NEG5V_44") (pintype "bidirectional"))
    )
    (net (code "149") (name "Net-(IC2-REFHP)") (class "Default")
      (node (ref "CREFHP-1") (pin "2") (pinfunction "2_2") (pintype "passive"))
      (node (ref "IC2") (pin "37") (pinfunction "REFHP_37") (pintype "bidirectional"))
    )
    (net (code "150") (name "Net-(LED1-A_RED)") (class "Default")
      (node (ref "LED1") (pin "2") (pinfunction "K_GREEN_2") (pintype "bidirectional"))
      (node (ref "LED1") (pin "3") (pinfunction "A_RED_3") (pintype "bidirectional"))
      (node (ref "R1") (pin "1") (pinfunction "1_1") (pintype "passive"))
    )
    (net (code "151") (name "Net-(LED2-A_RED)") (class "Default")
      (node (ref "LED2") (pin "2") (pinfunction "K_GREEN_2") (pintype "bidirectional"))
      (node (ref "LED2") (pin "3") (pinfunction "A_RED_3") (pintype "bidirectional"))
      (node (ref "R2") (pin "1") (pinfunction "1_1") (pintype "passive"))
    )
    (net (code "152") (name "Net-(LED3-A_RED)") (class "Default")
      (node (ref "LED3") (pin "2") (pinfunction "K_GREEN_2") (pintype "bidirectional"))
      (node (ref "LED3") (pin "3") (pinfunction "A_RED_3") (pintype "bidirectional"))
      (node (ref "R3") (pin "1") (pinfunction "1_1") (pintype "passive"))
    )
    (net (code "153") (name "Net-(LED4-A_RED)") (class "Default")
      (node (ref "LED4") (pin "2") (pinfunction "K_GREEN_2") (pintype "bidirectional"))
      (node (ref "LED4") (pin "3") (pinfunction "A_RED_3") (pintype "bidirectional"))
      (node (ref "R4") (pin "1") (pinfunction "1_1") (pintype "passive"))
    )
    (net (code "154") (name "Net-(LED5-A_RED)") (class "Default")
      (node (ref "LED5") (pin "2") (pinfunction "K_GREEN_2") (pintype "bidirectional"))
      (node (ref "LED5") (pin "3") (pinfunction "A_RED_3") (pintype "bidirectional"))
      (node (ref "R5") (pin "1") (pinfunction "1_1") (pintype "passive"))
    )
    (net (code "155") (name "Net-(LED6-A_RED)") (class "Default")
      (node (ref "LED6") (pin "2") (pinfunction "K_GREEN_2") (pintype "bidirectional"))
      (node (ref "LED6") (pin "3") (pinfunction "A_RED_3") (pintype "bidirectional"))
      (node (ref "R6") (pin "1") (pinfunction "1_1") (pintype "passive"))
    )
    (net (code "156") (name "Net-(LED7-A_RED)") (class "Default")
      (node (ref "LED7") (pin "2") (pinfunction "K_GREEN_2") (pintype "bidirectional"))
      (node (ref "LED7") (pin "3") (pinfunction "A_RED_3") (pintype "bidirectional"))
      (node (ref "R7") (pin "1") (pinfunction "1_1") (pintype "passive"))
    )
    (net (code "157") (name "Net-(LED8-A_RED)") (class "Default")
      (node (ref "LED8") (pin "2") (pinfunction "K_GREEN_2") (pintype "bidirectional"))
      (node (ref "LED8") (pin "3") (pinfunction "A_RED_3") (pintype "bidirectional"))
      (node (ref "R8") (pin "1") (pinfunction "1_1") (pintype "passive"))
    )
    (net (code "158") (name "Net-(LED9-A_RED)") (class "Default")
      (node (ref "LED9") (pin "2") (pinfunction "K_GREEN_2") (pintype "bidirectional"))
      (node (ref "LED9") (pin "3") (pinfunction "A_RED_3") (pintype "bidirectional"))
      (node (ref "R9") (pin "1") (pinfunction "1_1") (pintype "passive"))
    )
    (net (code "159") (name "Net-(LED10-A_RED)") (class "Default")
      (node (ref "LED10") (pin "2") (pinfunction "K_GREEN_2") (pintype "bidirectional"))
      (node (ref "LED10") (pin "3") (pinfunction "A_RED_3") (pintype "bidirectional"))
      (node (ref "R10") (pin "1") (pinfunction "1_1") (pintype "passive"))
    )
    (net (code "160") (name "Net-(LED11-A_RED)") (class "Default")
      (node (ref "LED11") (pin "2") (pinfunction "K_GREEN_2") (pintype "bidirectional"))
      (node (ref "LED11") (pin "3") (pinfunction "A_RED_3") (pintype "bidirectional"))
      (node (ref "R11") (pin "1") (pinfunction "1_1") (pintype "passive"))
    )
    (net (code "161") (name "Net-(LED12-A_RED)") (class "Default")
      (node (ref "LED12") (pin "2") (pinfunction "K_GREEN_2") (pintype "bidirectional"))
      (node (ref "LED12") (pin "3") (pinfunction "A_RED_3") (pintype "bidirectional"))
      (node (ref "R12") (pin "1") (pinfunction "1_1") (pintype "passive"))
    )
    (net (code "162") (name "Net-(LED13-A_RED)") (class "Default")
      (node (ref "LED13") (pin "2") (pinfunction "K_GREEN_2") (pintype "bidirectional"))
      (node (ref "LED13") (pin "3") (pinfunction "A_RED_3") (pintype "bidirectional"))
      (node (ref "R13") (pin "1") (pinfunction "1_1") (pintype "passive"))
    )
    (net (code "163") (name "Net-(LED14-A_RED)") (class "Default")
      (node (ref "LED14") (pin "2") (pinfunction "K_GREEN_2") (pintype "bidirectional"))
      (node (ref "LED14") (pin "3") (pinfunction "A_RED_3") (pintype "bidirectional"))
      (node (ref "R14") (pin "1") (pinfunction "1_1") (pintype "passive"))
    )
    (net (code "164") (name "Net-(LED15-A_RED)") (class "Default")
      (node (ref "LED15") (pin "2") (pinfunction "K_GREEN_2") (pintype "bidirectional"))
      (node (ref "LED15") (pin "3") (pinfunction "A_RED_3") (pintype "bidirectional"))
      (node (ref "R15") (pin "1") (pinfunction "1_1") (pintype "passive"))
    )
    (net (code "165") (name "Net-(LED16-A_RED)") (class "Default")
      (node (ref "LED16") (pin "2") (pinfunction "K_GREEN_2") (pintype "bidirectional"))
      (node (ref "LED16") (pin "3") (pinfunction "A_RED_3") (pintype "bidirectional"))
      (node (ref "R16") (pin "1") (pinfunction "1_1") (pintype "passive"))
    )
    (net (code "166") (name "Net-(LED17-A_RED)") (class "Default")
      (node (ref "LED17") (pin "2") (pinfunction "K_GREEN_2") (pintype "bidirectional"))
      (node (ref "LED17") (pin "3") (pinfunction "A_RED_3") (pintype "bidirectional"))
      (node (ref "R17") (pin "1") (pinfunction "1_1") (pintype "passive"))
    )
    (net (code "167") (name "Net-(LED18-A_RED)") (class "Default")
      (node (ref "LED18") (pin "2") (pinfunction "K_GREEN_2") (pintype "bidirectional"))
      (node (ref "LED18") (pin "3") (pinfunction "A_RED_3") (pintype "bidirectional"))
      (node (ref "R18") (pin "1") (pinfunction "1_1") (pintype "passive"))
    )
    (net (code "168") (name "Net-(LED19-A_RED)") (class "Default")
      (node (ref "LED19") (pin "2") (pinfunction "K_GREEN_2") (pintype "bidirectional"))
      (node (ref "LED19") (pin "3") (pinfunction "A_RED_3") (pintype "bidirectional"))
      (node (ref "R19") (pin "1") (pinfunction "1_1") (pintype "passive"))
    )
    (net (code "169") (name "Net-(LED20-A_RED)") (class "Default")
      (node (ref "LED20") (pin "2") (pinfunction "K_GREEN_2") (pintype "bidirectional"))
      (node (ref "LED20") (pin "3") (pinfunction "A_RED_3") (pintype "bidirectional"))
      (node (ref "R20") (pin "1") (pinfunction "1_1") (pintype "passive"))
    )
    (net (code "170") (name "Net-(LED21-A_RED)") (class "Default")
      (node (ref "LED21") (pin "2") (pinfunction "K_GREEN_2") (pintype "bidirectional"))
      (node (ref "LED21") (pin "3") (pinfunction "A_RED_3") (pintype "bidirectional"))
      (node (ref "R21") (pin "1") (pinfunction "1_1") (pintype "passive"))
    )
    (net (code "171") (name "Net-(LED22-A_RED)") (class "Default")
      (node (ref "LED22") (pin "2") (pinfunction "K_GREEN_2") (pintype "bidirectional"))
      (node (ref "LED22") (pin "3") (pinfunction "A_RED_3") (pintype "bidirectional"))
      (node (ref "R22") (pin "1") (pinfunction "1_1") (pintype "passive"))
    )
    (net (code "172") (name "Net-(SRA-S)") (class "Default")
      (node (ref "RCS1") (pin "1") (pinfunction "1_1") (pintype "passive"))
      (node (ref "SR") (pin "1") (pinfunction "S_1") (pintype "passive"))
    )
    (net (code "173") (name "Net-(SRB-S)") (class "Default")
      (node (ref "RCS2") (pin "1") (pinfunction "1_1") (pintype "passive"))
      (node (ref "SR") (pin "2") (pinfunction "S_2") (pintype "passive"))
    )
    (net (code "174") (name "unconnected-(CBHD-S-Pad12)") (class "Default")
      (node (ref "CBH") (pin "12") (pinfunction "S_12") (pintype "passive"))
    )
    (net (code "175") (name "unconnected-(CBLD-S-Pad12)") (class "Default")
      (node (ref "CBL") (pin "12") (pinfunction "S_12") (pintype "passive"))
    )
    (net (code "176") (name "unconnected-(IC2-BBN(SRN)-Pad63)") (class "Default")
      (node (ref "IC2") (pin "63") (pinfunction "BBN(SRN)_63") (pintype "bidirectional"))
    )
    (net (code "177") (name "unconnected-(IC2-BBP(SRP)-Pad64)") (class "Default")
      (node (ref "IC2") (pin "64") (pinfunction "BBP(SRP)_64") (pintype "bidirectional"))
    )
    (net (code "178") (name "unconnected-(IC2-NFAULT-Pad62)") (class "Default")
      (node (ref "IC2") (pin "62") (pinfunction "NFAULT_62") (pintype "bidirectional"))
    )
    (net (code "179") (name "unconnected-(IC2-TX-Pad53)") (class "Default")
      (node (ref "IC2") (pin "53") (pinfunction "TX_53") (pintype "bidirectional"))
    )
    (net (code "180") (name "unconnected-(VCHD-S-Pad12)") (class "Default")
      (node (ref "VCH") (pin "12") (pinfunction "S_12") (pintype "passive"))
    )
    (net (code "181") (name "unconnected-(VCLD-S-Pad12)") (class "Default")
      (node (ref "VCL") (pin "12") (pinfunction "S_12") (pintype "passive"))
    )
  )
)
